# PCB-CMB-5-SHLD.net
KiCad netlist of a schematic drawn in EAGLE
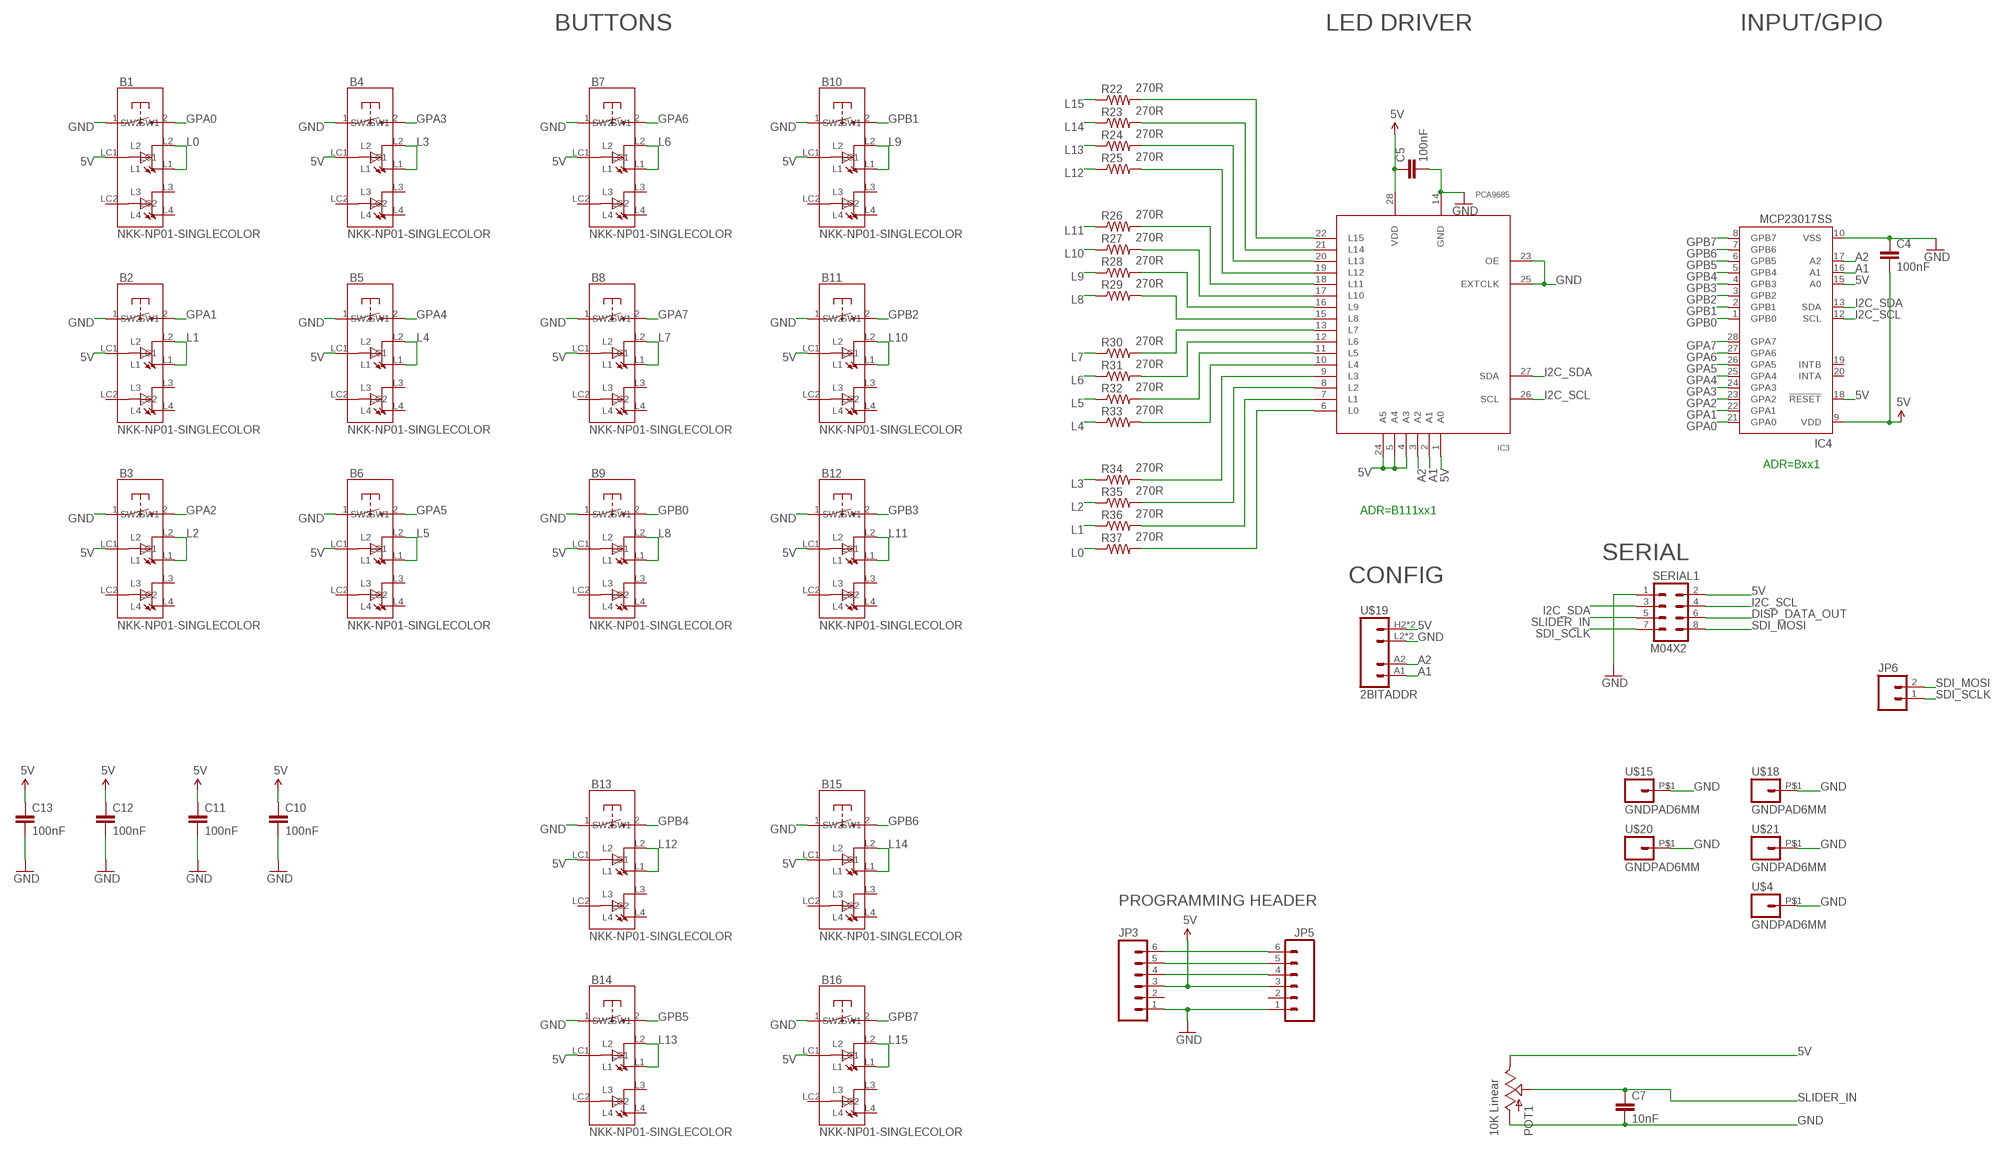
[diagram p0: schematic, sheet 1, part 1 of 3]
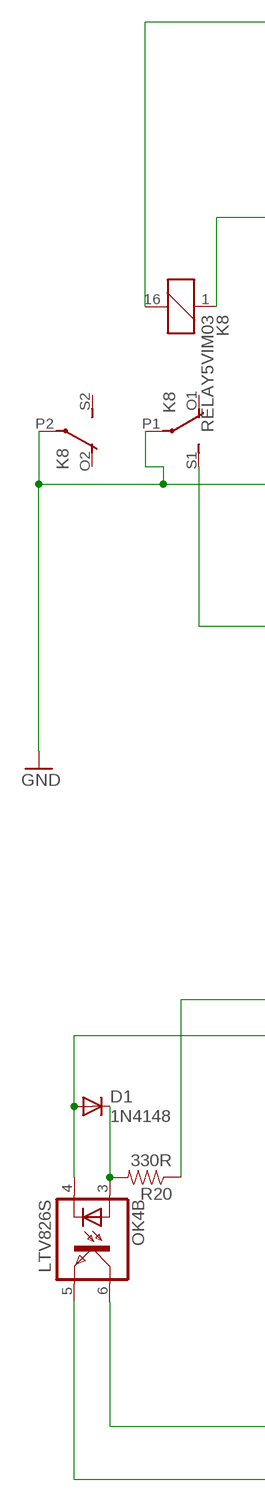
[diagram p1: schematic, sheet 1, part 2 of 3]
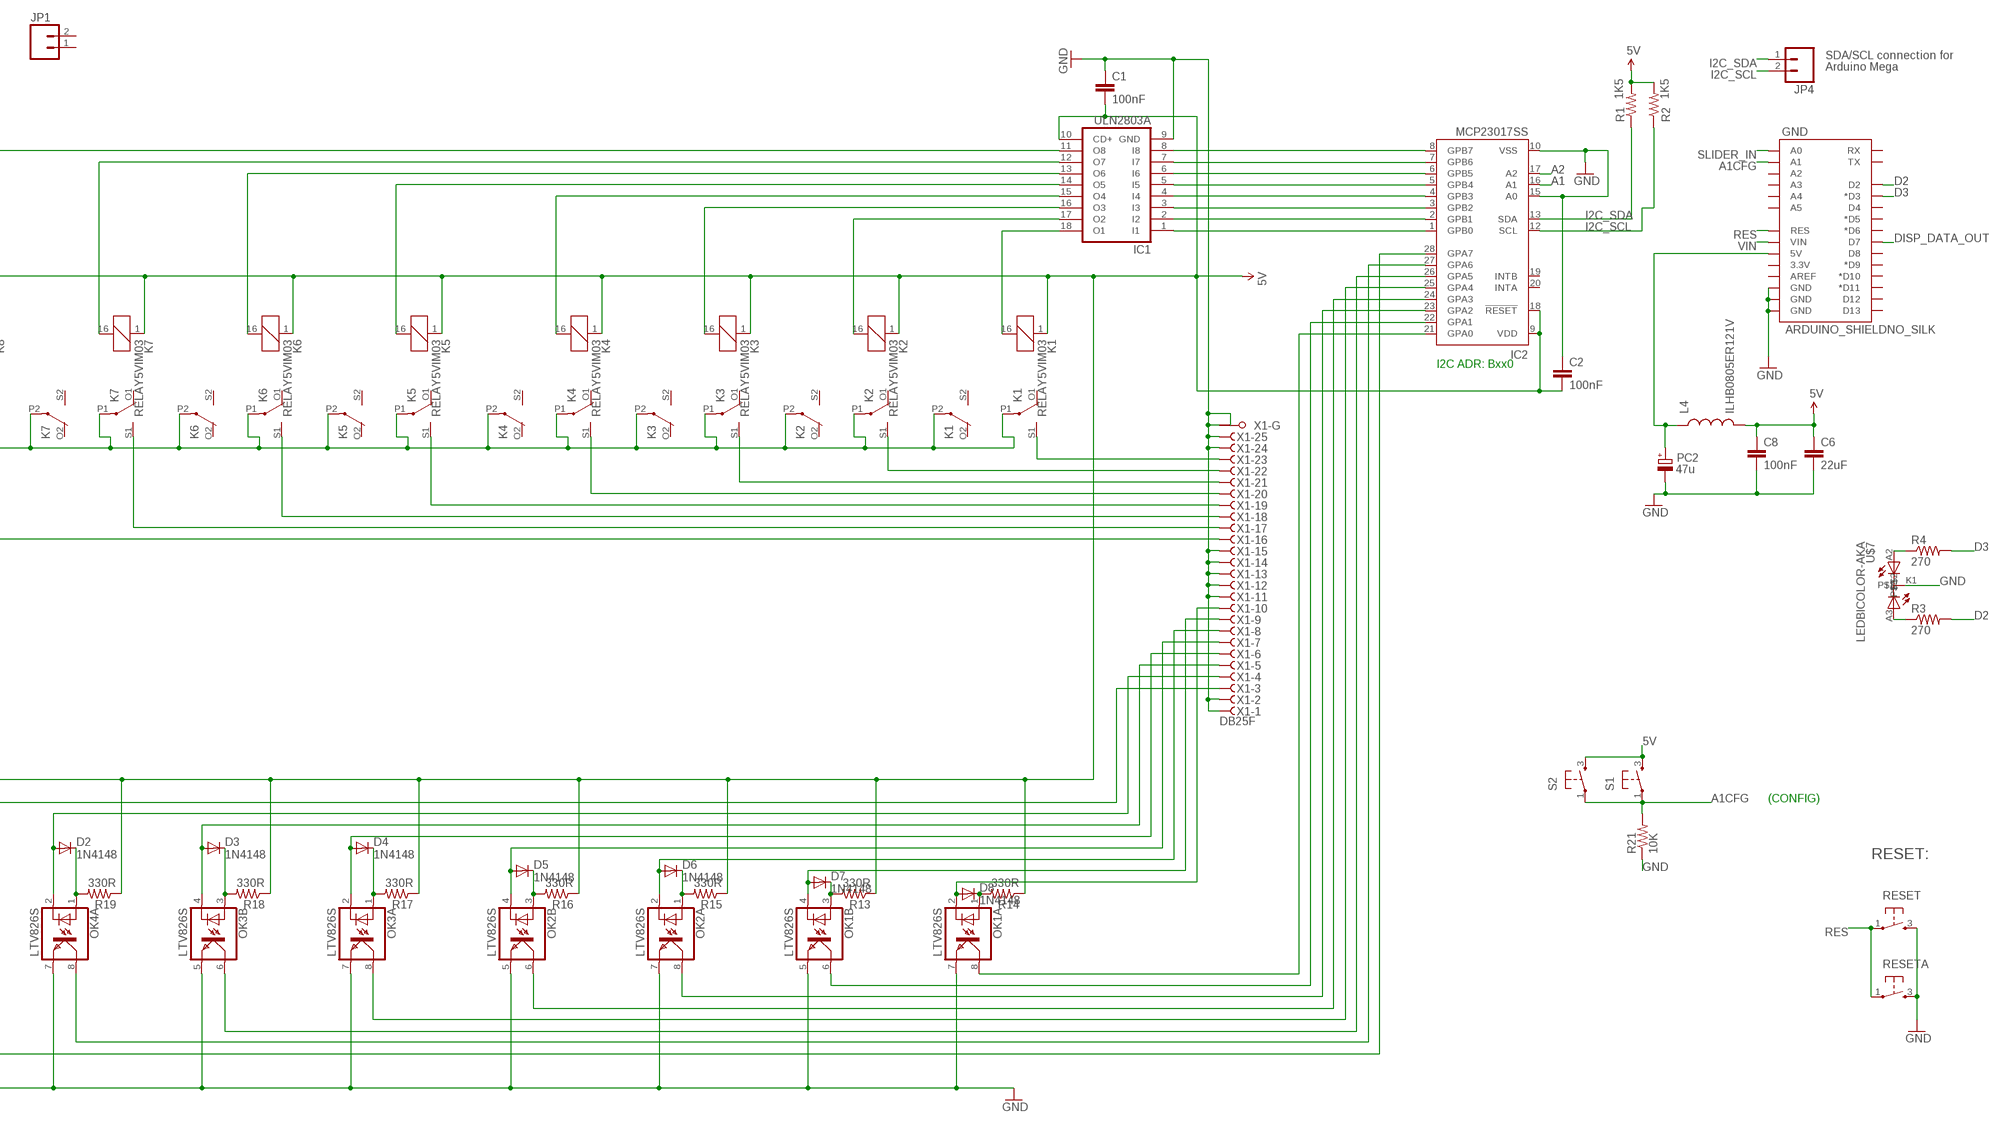
[diagram p2: schematic, sheet 1, part 3 of 3]

(export (version "E")
  (design (tool "Eeschema 10.0.6"))
  (components
    (comp (ref "B1")
      (value "NKK-NP01-SINGLECOLOR")
      (footprint "eagle-import:NKK-NP01")
      (libsource (lib "eagle-import") (part "NKK-NP01-SINGLECOLOR"))
    )
    (comp (ref "B2")
      (value "NKK-NP01-SINGLECOLOR")
      (footprint "eagle-import:NKK-NP01")
      (libsource (lib "eagle-import") (part "NKK-NP01-SINGLECOLOR"))
    )
    (comp (ref "B3")
      (value "NKK-NP01-SINGLECOLOR")
      (footprint "eagle-import:NKK-NP01")
      (libsource (lib "eagle-import") (part "NKK-NP01-SINGLECOLOR"))
    )
    (comp (ref "B4")
      (value "NKK-NP01-SINGLECOLOR")
      (footprint "eagle-import:NKK-NP01")
      (libsource (lib "eagle-import") (part "NKK-NP01-SINGLECOLOR"))
    )
    (comp (ref "B5")
      (value "NKK-NP01-SINGLECOLOR")
      (footprint "eagle-import:NKK-NP01")
      (libsource (lib "eagle-import") (part "NKK-NP01-SINGLECOLOR"))
    )
    (comp (ref "B6")
      (value "NKK-NP01-SINGLECOLOR")
      (footprint "eagle-import:NKK-NP01")
      (libsource (lib "eagle-import") (part "NKK-NP01-SINGLECOLOR"))
    )
    (comp (ref "B7")
      (value "NKK-NP01-SINGLECOLOR")
      (footprint "eagle-import:NKK-NP01")
      (libsource (lib "eagle-import") (part "NKK-NP01-SINGLECOLOR"))
    )
    (comp (ref "B8")
      (value "NKK-NP01-SINGLECOLOR")
      (footprint "eagle-import:NKK-NP01")
      (libsource (lib "eagle-import") (part "NKK-NP01-SINGLECOLOR"))
    )
    (comp (ref "B9")
      (value "NKK-NP01-SINGLECOLOR")
      (footprint "eagle-import:NKK-NP01")
      (libsource (lib "eagle-import") (part "NKK-NP01-SINGLECOLOR"))
    )
    (comp (ref "B10")
      (value "NKK-NP01-SINGLECOLOR")
      (footprint "eagle-import:NKK-NP01")
      (libsource (lib "eagle-import") (part "NKK-NP01-SINGLECOLOR"))
    )
    (comp (ref "B11")
      (value "NKK-NP01-SINGLECOLOR")
      (footprint "eagle-import:NKK-NP01")
      (libsource (lib "eagle-import") (part "NKK-NP01-SINGLECOLOR"))
    )
    (comp (ref "B12")
      (value "NKK-NP01-SINGLECOLOR")
      (footprint "eagle-import:NKK-NP01")
      (libsource (lib "eagle-import") (part "NKK-NP01-SINGLECOLOR"))
    )
    (comp (ref "B13")
      (value "NKK-NP01-SINGLECOLOR")
      (footprint "eagle-import:NKK-NP01")
      (libsource (lib "eagle-import") (part "NKK-NP01-SINGLECOLOR"))
    )
    (comp (ref "B14")
      (value "NKK-NP01-SINGLECOLOR")
      (footprint "eagle-import:NKK-NP01")
      (libsource (lib "eagle-import") (part "NKK-NP01-SINGLECOLOR"))
    )
    (comp (ref "B15")
      (value "NKK-NP01-SINGLECOLOR")
      (footprint "eagle-import:NKK-NP01")
      (libsource (lib "eagle-import") (part "NKK-NP01-SINGLECOLOR"))
    )
    (comp (ref "B16")
      (value "NKK-NP01-SINGLECOLOR")
      (footprint "eagle-import:NKK-NP01")
      (libsource (lib "eagle-import") (part "NKK-NP01-SINGLECOLOR"))
    )
    (comp (ref "C1")
      (value "100nF")
      (footprint "eagle-import:0805")
      (libsource (lib "eagle-import") (part "CAP0805"))
    )
    (comp (ref "C2")
      (value "100nF")
      (footprint "eagle-import:0603-CAP")
      (libsource (lib "eagle-import") (part "CAP0603-CAP"))
    )
    (comp (ref "C4")
      (value "100nF")
      (footprint "eagle-import:0603-CAP")
      (libsource (lib "eagle-import") (part "CAP0603-CAP"))
    )
    (comp (ref "C5")
      (value "100nF")
      (footprint "eagle-import:0603-CAP")
      (libsource (lib "eagle-import") (part "CAP0603-CAP"))
    )
    (comp (ref "C6")
      (value "22uF")
      (footprint "eagle-import:0805")
      (libsource (lib "eagle-import") (part "CAP0805"))
    )
    (comp (ref "C7")
      (value "10nF")
      (footprint "eagle-import:0603-CAP")
      (libsource (lib "eagle-import") (part "CAP0603-CAP"))
    )
    (comp (ref "C8")
      (value "100nF")
      (footprint "eagle-import:0603-CAP")
      (libsource (lib "eagle-import") (part "CAP0603-CAP"))
    )
    (comp (ref "C10")
      (value "100nF")
      (footprint "eagle-import:0603-CAP")
      (libsource (lib "eagle-import") (part "CAP0603-CAP"))
    )
    (comp (ref "C11")
      (value "100nF")
      (footprint "eagle-import:0603-CAP")
      (libsource (lib "eagle-import") (part "CAP0603-CAP"))
    )
    (comp (ref "C12")
      (value "100nF")
      (footprint "eagle-import:0603-CAP")
      (libsource (lib "eagle-import") (part "CAP0603-CAP"))
    )
    (comp (ref "C13")
      (value "100nF")
      (footprint "eagle-import:0603-CAP")
      (libsource (lib "eagle-import") (part "CAP0603-CAP"))
    )
    (comp (ref "D1")
      (value "1N4148")
      (footprint "eagle-import:SOD-323")
      (libsource (lib "eagle-import") (part "DIODESOD"))
    )
    (comp (ref "D2")
      (value "1N4148")
      (footprint "eagle-import:SOD-323")
      (libsource (lib "eagle-import") (part "DIODESOD"))
    )
    (comp (ref "D3")
      (value "1N4148")
      (footprint "eagle-import:SOD-323")
      (libsource (lib "eagle-import") (part "DIODESOD"))
    )
    (comp (ref "D4")
      (value "1N4148")
      (footprint "eagle-import:SOD-323")
      (libsource (lib "eagle-import") (part "DIODESOD"))
    )
    (comp (ref "D5")
      (value "1N4148")
      (footprint "eagle-import:SOD-323")
      (libsource (lib "eagle-import") (part "DIODESOD"))
    )
    (comp (ref "D6")
      (value "1N4148")
      (footprint "eagle-import:SOD-323")
      (libsource (lib "eagle-import") (part "DIODESOD"))
    )
    (comp (ref "D7")
      (value "1N4148")
      (footprint "eagle-import:SOD-323")
      (libsource (lib "eagle-import") (part "DIODESOD"))
    )
    (comp (ref "D8")
      (value "1N4148")
      (footprint "eagle-import:SOD-323")
      (libsource (lib "eagle-import") (part "DIODESOD"))
    )
    (comp (ref "GND")
      (value "ARDUINO_SHIELDNO_SILK")
      (footprint "eagle-import:DUEMILANOVE_VIAS")
      (libsource (lib "eagle-import") (part "ARDUINO_SHIELDNO_SILK"))
    )
    (comp (ref "IC1")
      (value "ULN2803A")
      (footprint "eagle-import:SO18W")
      (libsource (lib "eagle-import") (part "ULN2803ASO18W"))
    )
    (comp (ref "IC2")
      (value "MCP23017SS")
      (footprint "eagle-import:SSOP28")
      (fields (field (name "MF") "MICROCHIP") (field (name "MPN") "MCP23017-E/SS"))
      (libsource (lib "eagle-import") (part "MCP23017SS"))
    )
    (comp (ref "IC3")
      (value "PCA9685")
      (footprint "eagle-import:TSSOP28")
      (libsource (lib "eagle-import") (part "PCA9685"))
    )
    (comp (ref "IC4")
      (value "MCP23017SS")
      (footprint "eagle-import:SSOP28")
      (fields
        (field (name "MF") "MICROCHIP")
        (field (name "MPN") "MCP23017-E/SS")
        (field (name "MPN_1") "MCP23017-E/SS")
        (field (name "OC_FARNELL") "1467674")
        (field (name "OC_NEWARK") "31K2960")
      )
      (libsource (lib "eagle-import") (part "MCP23017SS"))
    )
    (comp (ref "JP1")
      (value "M02PTH")
      (footprint "eagle-import:1X02")
      (libsource (lib "eagle-import") (part "M02PTH"))
    )
    (comp (ref "JP3")
      (value "M06POLAR")
      (footprint "eagle-import:MOLEX-1X6")
      (libsource (lib "eagle-import") (part "M06POLAR"))
    )
    (comp (ref "JP4")
      (value "M02PTH")
      (footprint "eagle-import:1X02")
      (libsource (lib "eagle-import") (part "M02PTH"))
    )
    (comp (ref "JP5")
      (value "M06POLAR")
      (footprint "eagle-import:MOLEX-1X6")
      (libsource (lib "eagle-import") (part "M06POLAR"))
    )
    (comp (ref "JP6")
      (value "M02PTH")
      (footprint "eagle-import:1X02")
      (libsource (lib "eagle-import") (part "M02PTH"))
    )
    (comp (ref "K1")
      (value "RELAY5VIM03")
      (footprint "eagle-import:DS2Y")
      (libsource (lib "eagle-import") (part "RELAY5VIM03"))
    )
    (comp (ref "K2")
      (value "RELAY5VIM03")
      (footprint "eagle-import:DS2Y")
      (libsource (lib "eagle-import") (part "RELAY5VIM03"))
    )
    (comp (ref "K3")
      (value "RELAY5VIM03")
      (footprint "eagle-import:DS2Y")
      (libsource (lib "eagle-import") (part "RELAY5VIM03"))
    )
    (comp (ref "K4")
      (value "RELAY5VIM03")
      (footprint "eagle-import:DS2Y")
      (libsource (lib "eagle-import") (part "RELAY5VIM03"))
    )
    (comp (ref "K5")
      (value "RELAY5VIM03")
      (footprint "eagle-import:DS2Y")
      (libsource (lib "eagle-import") (part "RELAY5VIM03"))
    )
    (comp (ref "K6")
      (value "RELAY5VIM03")
      (footprint "eagle-import:DS2Y")
      (libsource (lib "eagle-import") (part "RELAY5VIM03"))
    )
    (comp (ref "K7")
      (value "RELAY5VIM03")
      (footprint "eagle-import:DS2Y")
      (libsource (lib "eagle-import") (part "RELAY5VIM03"))
    )
    (comp (ref "K8")
      (value "RELAY5VIM03")
      (footprint "eagle-import:DS2Y")
      (libsource (lib "eagle-import") (part "RELAY5VIM03"))
    )
    (comp (ref "L4")
      (value "ILHB0805ER121V")
      (footprint "eagle-import:0805")
      (libsource (lib "eagle-import") (part "INDUCTOR0805"))
    )
    (comp (ref "OK1")
      (value "LTV826S")
      (footprint "eagle-import:DIL8-SMD")
      (libsource (lib "eagle-import") (part "LTV826S"))
    )
    (comp (ref "OK2")
      (value "LTV826S")
      (footprint "eagle-import:DIL8-SMD")
      (libsource (lib "eagle-import") (part "LTV826S"))
    )
    (comp (ref "OK3")
      (value "LTV826S")
      (footprint "eagle-import:DIL8-SMD")
      (libsource (lib "eagle-import") (part "LTV826S"))
    )
    (comp (ref "OK4")
      (value "LTV826S")
      (footprint "eagle-import:DIL8-SMD")
      (libsource (lib "eagle-import") (part "LTV826S"))
    )
    (comp (ref "PC2")
      (value "47u")
      (footprint "eagle-import:PANASONIC_D")
      (libsource (lib "eagle-import") (part "CPOL-EUD"))
    )
    (comp (ref "POT1")
      (value "10K Linear")
      (footprint "eagle-import:SLIDER20")
      (libsource (lib "eagle-import") (part "SLIDER20"))
    )
    (comp (ref "R1")
      (value "1K5")
      (footprint "eagle-import:0603-RES")
      (libsource (lib "eagle-import") (part "RESISTOR0603-RES"))
    )
    (comp (ref "R2")
      (value "1K5")
      (footprint "eagle-import:0603-RES")
      (libsource (lib "eagle-import") (part "RESISTOR0603-RES"))
    )
    (comp (ref "R3")
      (value "270")
      (footprint "eagle-import:0603-RES")
      (libsource (lib "eagle-import") (part "RESISTOR0603-RES"))
    )
    (comp (ref "R4")
      (value "270")
      (footprint "eagle-import:0603-RES")
      (libsource (lib "eagle-import") (part "RESISTOR0603-RES"))
    )
    (comp (ref "R13")
      (value "330R")
      (footprint "eagle-import:0603-RES")
      (libsource (lib "eagle-import") (part "RESISTOR0603-RES"))
    )
    (comp (ref "R14")
      (value "330R")
      (footprint "eagle-import:0603-RES")
      (libsource (lib "eagle-import") (part "RESISTOR0603-RES"))
    )
    (comp (ref "R15")
      (value "330R")
      (footprint "eagle-import:0603-RES")
      (libsource (lib "eagle-import") (part "RESISTOR0603-RES"))
    )
    (comp (ref "R16")
      (value "330R")
      (footprint "eagle-import:0603-RES")
      (libsource (lib "eagle-import") (part "RESISTOR0603-RES"))
    )
    (comp (ref "R17")
      (value "330R")
      (footprint "eagle-import:0603-RES")
      (libsource (lib "eagle-import") (part "RESISTOR0603-RES"))
    )
    (comp (ref "R18")
      (value "330R")
      (footprint "eagle-import:0603-RES")
      (libsource (lib "eagle-import") (part "RESISTOR0603-RES"))
    )
    (comp (ref "R19")
      (value "330R")
      (footprint "eagle-import:0603-RES")
      (libsource (lib "eagle-import") (part "RESISTOR0603-RES"))
    )
    (comp (ref "R20")
      (value "330R")
      (footprint "eagle-import:0603-RES")
      (libsource (lib "eagle-import") (part "RESISTOR0603-RES"))
    )
    (comp (ref "R21")
      (value "10K")
      (footprint "eagle-import:0603-RES")
      (libsource (lib "eagle-import") (part "RESISTOR0603-RES"))
    )
    (comp (ref "R22")
      (value "270R")
      (footprint "eagle-import:0603-RES")
      (libsource (lib "eagle-import") (part "RESISTOR0603-RES"))
    )
    (comp (ref "R23")
      (value "270R")
      (footprint "eagle-import:0603-RES")
      (libsource (lib "eagle-import") (part "RESISTOR0603-RES"))
    )
    (comp (ref "R24")
      (value "270R")
      (footprint "eagle-import:0603-RES")
      (libsource (lib "eagle-import") (part "RESISTOR0603-RES"))
    )
    (comp (ref "R25")
      (value "270R")
      (footprint "eagle-import:0603-RES")
      (libsource (lib "eagle-import") (part "RESISTOR0603-RES"))
    )
    (comp (ref "R26")
      (value "270R")
      (footprint "eagle-import:0603-RES")
      (libsource (lib "eagle-import") (part "RESISTOR0603-RES"))
    )
    (comp (ref "R27")
      (value "270R")
      (footprint "eagle-import:0603-RES")
      (libsource (lib "eagle-import") (part "RESISTOR0603-RES"))
    )
    (comp (ref "R28")
      (value "270R")
      (footprint "eagle-import:0603-RES")
      (libsource (lib "eagle-import") (part "RESISTOR0603-RES"))
    )
    (comp (ref "R29")
      (value "270R")
      (footprint "eagle-import:0603-RES")
      (libsource (lib "eagle-import") (part "RESISTOR0603-RES"))
    )
    (comp (ref "R30")
      (value "270R")
      (footprint "eagle-import:0603-RES")
      (libsource (lib "eagle-import") (part "RESISTOR0603-RES"))
    )
    (comp (ref "R31")
      (value "270R")
      (footprint "eagle-import:0603-RES")
      (libsource (lib "eagle-import") (part "RESISTOR0603-RES"))
    )
    (comp (ref "R32")
      (value "270R")
      (footprint "eagle-import:0603-RES")
      (libsource (lib "eagle-import") (part "RESISTOR0603-RES"))
    )
    (comp (ref "R33")
      (value "270R")
      (footprint "eagle-import:0603-RES")
      (libsource (lib "eagle-import") (part "RESISTOR0603-RES"))
    )
    (comp (ref "R34")
      (value "270R")
      (footprint "eagle-import:0603-RES")
      (libsource (lib "eagle-import") (part "RESISTOR0603-RES"))
    )
    (comp (ref "R35")
      (value "270R")
      (footprint "eagle-import:0603-RES")
      (libsource (lib "eagle-import") (part "RESISTOR0603-RES"))
    )
    (comp (ref "R36")
      (value "270R")
      (footprint "eagle-import:0603-RES")
      (libsource (lib "eagle-import") (part "RESISTOR0603-RES"))
    )
    (comp (ref "R37")
      (value "270R")
      (footprint "eagle-import:0603-RES")
      (libsource (lib "eagle-import") (part "RESISTOR0603-RES"))
    )
    (comp (ref "RESET")
      (value "TAC_SWITCH")
      (footprint "eagle-import:PUSHBUTTON")
      (libsource (lib "eagle-import") (part "TAC_SWITCH"))
    )
    (comp (ref "RESETA")
      (value "TAC_SWITCH")
      (footprint "eagle-import:PUSHBUTTON")
      (libsource (lib "eagle-import") (part "TAC_SWITCH"))
    )
    (comp (ref "S1")
      (value "TAC_SWITCH")
      (footprint "eagle-import:PUSHBUTTON")
      (libsource (lib "eagle-import") (part "TAC_SWITCH"))
    )
    (comp (ref "S2")
      (value "TAC_SWITCH")
      (footprint "eagle-import:PUSHBUTTON")
      (libsource (lib "eagle-import") (part "TAC_SWITCH"))
    )
    (comp (ref "SERIAL1")
      (value "M04X2")
      (footprint "eagle-import:2X4")
      (libsource (lib "eagle-import") (part "M04X2"))
    )
    (comp (ref "U$4")
      (value "GNDPAD6MM")
      (footprint "eagle-import:3.2MMPAD6MM")
      (libsource (lib "eagle-import") (part "GNDPAD6MM"))
    )
    (comp (ref "U$7")
      (value "LEDBICOLOR-AKA")
      (footprint "eagle-import:LED5MM-BICOLOR")
      (libsource (lib "eagle-import") (part "LEDBICOLOR-AKA"))
    )
    (comp (ref "U$15")
      (value "GNDPAD6MM")
      (footprint "eagle-import:3.2MMPAD6MM")
      (libsource (lib "eagle-import") (part "GNDPAD6MM"))
    )
    (comp (ref "U$18")
      (value "GNDPAD6MM")
      (footprint "eagle-import:3.2MMPAD6MM")
      (libsource (lib "eagle-import") (part "GNDPAD6MM"))
    )
    (comp (ref "U$19")
      (value "2BITADDR")
      (footprint "eagle-import:2BITADDR")
      (libsource (lib "eagle-import") (part "2BITADDR"))
    )
    (comp (ref "U$20")
      (value "GNDPAD6MM")
      (footprint "eagle-import:3.2MMPAD6MM")
      (libsource (lib "eagle-import") (part "GNDPAD6MM"))
    )
    (comp (ref "U$21")
      (value "GNDPAD6MM")
      (footprint "eagle-import:3.2MMPAD6MM")
      (libsource (lib "eagle-import") (part "GNDPAD6MM"))
    )
    (comp (ref "X1")
      (value "DB25F")
      (footprint "eagle-import:F25HP")
      (libsource (lib "eagle-import") (part "F25HPS"))
    )
  )
  (nets
    (net (code "1") (name "5V") (class "Default")
      (node (ref "B1") (pin "LC1") (pinfunction "LC1_LC1") (pintype "bidirectional"))
      (node (ref "B10") (pin "LC1") (pinfunction "LC1_LC1") (pintype "bidirectional"))
      (node (ref "B11") (pin "LC1") (pinfunction "LC1_LC1") (pintype "bidirectional"))
      (node (ref "B12") (pin "LC1") (pinfunction "LC1_LC1") (pintype "bidirectional"))
      (node (ref "B13") (pin "LC1") (pinfunction "LC1_LC1") (pintype "bidirectional"))
      (node (ref "B14") (pin "LC1") (pinfunction "LC1_LC1") (pintype "bidirectional"))
      (node (ref "B15") (pin "LC1") (pinfunction "LC1_LC1") (pintype "bidirectional"))
      (node (ref "B16") (pin "LC1") (pinfunction "LC1_LC1") (pintype "bidirectional"))
      (node (ref "B2") (pin "LC1") (pinfunction "LC1_LC1") (pintype "bidirectional"))
      (node (ref "B3") (pin "LC1") (pinfunction "LC1_LC1") (pintype "bidirectional"))
      (node (ref "B4") (pin "LC1") (pinfunction "LC1_LC1") (pintype "bidirectional"))
      (node (ref "B5") (pin "LC1") (pinfunction "LC1_LC1") (pintype "bidirectional"))
      (node (ref "B6") (pin "LC1") (pinfunction "LC1_LC1") (pintype "bidirectional"))
      (node (ref "B7") (pin "LC1") (pinfunction "LC1_LC1") (pintype "bidirectional"))
      (node (ref "B8") (pin "LC1") (pinfunction "LC1_LC1") (pintype "bidirectional"))
      (node (ref "B9") (pin "LC1") (pinfunction "LC1_LC1") (pintype "bidirectional"))
      (node (ref "C1") (pin "2") (pinfunction "2_2") (pintype "passive"))
      (node (ref "C10") (pin "1") (pinfunction "1_1") (pintype "passive"))
      (node (ref "C11") (pin "1") (pinfunction "1_1") (pintype "passive"))
      (node (ref "C12") (pin "1") (pinfunction "1_1") (pintype "passive"))
      (node (ref "C13") (pin "1") (pinfunction "1_1") (pintype "passive"))
      (node (ref "C2") (pin "2") (pinfunction "2_2") (pintype "passive"))
      (node (ref "C4") (pin "2") (pinfunction "2_2") (pintype "passive"))
      (node (ref "C5") (pin "1") (pinfunction "1_1") (pintype "passive"))
      (node (ref "C6") (pin "1") (pinfunction "1_1") (pintype "passive"))
      (node (ref "C8") (pin "1") (pinfunction "1_1") (pintype "passive"))
      (node (ref "IC1") (pin "10") (pinfunction "CD+_10") (pintype "passive"))
      (node (ref "IC2") (pin "18") (pinfunction "~{RESET}_18") (pintype "input"))
      (node (ref "IC2") (pin "9") (pinfunction "VDD_9") (pintype "power_in"))
      (node (ref "IC3") (pin "1") (pinfunction "A0_1") (pintype "input"))
      (node (ref "IC3") (pin "24") (pinfunction "A5_24") (pintype "input"))
      (node (ref "IC3") (pin "28") (pinfunction "VDD_28") (pintype "power_in"))
      (node (ref "IC3") (pin "4") (pinfunction "A3_4") (pintype "input"))
      (node (ref "IC3") (pin "5") (pinfunction "A4_5") (pintype "input"))
      (node (ref "IC4") (pin "15") (pinfunction "A0_15") (pintype "input"))
      (node (ref "IC4") (pin "18") (pinfunction "~{RESET}_18") (pintype "input"))
      (node (ref "IC4") (pin "9") (pinfunction "VDD_9") (pintype "power_in"))
      (node (ref "JP3") (pin "3") (pinfunction "3_3") (pintype "passive"))
      (node (ref "JP5") (pin "3") (pinfunction "3_3") (pintype "passive"))
      (node (ref "K1") (pin "1") (pinfunction "1_1") (pintype "passive"))
      (node (ref "K2") (pin "1") (pinfunction "1_1") (pintype "passive"))
      (node (ref "K3") (pin "1") (pinfunction "1_1") (pintype "passive"))
      (node (ref "K4") (pin "1") (pinfunction "1_1") (pintype "passive"))
      (node (ref "K5") (pin "1") (pinfunction "1_1") (pintype "passive"))
      (node (ref "K6") (pin "1") (pinfunction "1_1") (pintype "passive"))
      (node (ref "K7") (pin "1") (pinfunction "1_1") (pintype "passive"))
      (node (ref "K8") (pin "1") (pinfunction "1_1") (pintype "passive"))
      (node (ref "L4") (pin "2") (pinfunction "2_2") (pintype "passive"))
      (node (ref "POT1") (pin "1") (pinfunction "E_1") (pintype "passive"))
      (node (ref "R1") (pin "2") (pinfunction "2_2") (pintype "passive"))
      (node (ref "R13") (pin "1") (pinfunction "1_1") (pintype "passive"))
      (node (ref "R14") (pin "1") (pinfunction "1_1") (pintype "passive"))
      (node (ref "R15") (pin "1") (pinfunction "1_1") (pintype "passive"))
      (node (ref "R16") (pin "1") (pinfunction "1_1") (pintype "passive"))
      (node (ref "R17") (pin "1") (pinfunction "1_1") (pintype "passive"))
      (node (ref "R18") (pin "1") (pinfunction "1_1") (pintype "passive"))
      (node (ref "R19") (pin "1") (pinfunction "1_1") (pintype "passive"))
      (node (ref "R2") (pin "2") (pinfunction "2_2") (pintype "passive"))
      (node (ref "R20") (pin "1") (pinfunction "1_1") (pintype "passive"))
      (node (ref "S1") (pin "3") (pinfunction "3_3") (pintype "passive"))
      (node (ref "S2") (pin "3") (pinfunction "3_3") (pintype "passive"))
      (node (ref "SERIAL1") (pin "2") (pinfunction "2_2") (pintype "passive"))
      (node (ref "U$19") (pin "H2") (pinfunction "VCC_H2") (pintype "passive"))
      (node (ref "U$19") (pin "H3") (pinfunction "VCC_H3") (pintype "passive"))
    )
    (net (code "2") (name "A1") (class "Default")
      (node (ref "IC2") (pin "16") (pinfunction "A1_16") (pintype "input"))
      (node (ref "IC3") (pin "2") (pinfunction "A1_2") (pintype "input"))
      (node (ref "IC4") (pin "16") (pinfunction "A1_16") (pintype "input"))
      (node (ref "U$19") (pin "A1") (pinfunction "A1_A1") (pintype "passive"))
    )
    (net (code "3") (name "A1CFG") (class "Default")
      (node (ref "GND") (pin "A1") (pinfunction "A1_A1") (pintype "bidirectional"))
      (node (ref "R21") (pin "2") (pinfunction "2_2") (pintype "passive"))
      (node (ref "S1") (pin "1") (pinfunction "1_1") (pintype "passive"))
      (node (ref "S2") (pin "1") (pinfunction "1_1") (pintype "passive"))
    )
    (net (code "4") (name "A2") (class "Default")
      (node (ref "IC2") (pin "17") (pinfunction "A2_17") (pintype "input"))
      (node (ref "IC3") (pin "3") (pinfunction "A2_3") (pintype "input"))
      (node (ref "IC4") (pin "17") (pinfunction "A2_17") (pintype "input"))
      (node (ref "U$19") (pin "A2") (pinfunction "A2_A2") (pintype "passive"))
    )
    (net (code "5") (name "D2") (class "Default")
      (node (ref "GND") (pin "D2") (pinfunction "D2_D2") (pintype "bidirectional"))
      (node (ref "R3") (pin "2") (pinfunction "2_2") (pintype "passive"))
    )
    (net (code "6") (name "D3") (class "Default")
      (node (ref "GND") (pin "D3") (pinfunction "*D3_D3") (pintype "bidirectional"))
      (node (ref "R4") (pin "2") (pinfunction "2_2") (pintype "passive"))
    )
    (net (code "7") (name "DISP_DATA_OUT") (class "Default")
      (node (ref "GND") (pin "D7") (pinfunction "D7_D7") (pintype "bidirectional"))
      (node (ref "SERIAL1") (pin "6") (pinfunction "6_6") (pintype "passive"))
    )
    (net (code "8") (name "GND") (class "Default")
      (node (ref "B1") (pin "1") (pinfunction "SW1_1") (pintype "bidirectional"))
      (node (ref "B10") (pin "1") (pinfunction "SW1_1") (pintype "bidirectional"))
      (node (ref "B11") (pin "1") (pinfunction "SW1_1") (pintype "bidirectional"))
      (node (ref "B12") (pin "1") (pinfunction "SW1_1") (pintype "bidirectional"))
      (node (ref "B13") (pin "1") (pinfunction "SW1_1") (pintype "bidirectional"))
      (node (ref "B14") (pin "1") (pinfunction "SW1_1") (pintype "bidirectional"))
      (node (ref "B15") (pin "1") (pinfunction "SW1_1") (pintype "bidirectional"))
      (node (ref "B16") (pin "1") (pinfunction "SW1_1") (pintype "bidirectional"))
      (node (ref "B2") (pin "1") (pinfunction "SW1_1") (pintype "bidirectional"))
      (node (ref "B3") (pin "1") (pinfunction "SW1_1") (pintype "bidirectional"))
      (node (ref "B4") (pin "1") (pinfunction "SW1_1") (pintype "bidirectional"))
      (node (ref "B5") (pin "1") (pinfunction "SW1_1") (pintype "bidirectional"))
      (node (ref "B6") (pin "1") (pinfunction "SW1_1") (pintype "bidirectional"))
      (node (ref "B7") (pin "1") (pinfunction "SW1_1") (pintype "bidirectional"))
      (node (ref "B8") (pin "1") (pinfunction "SW1_1") (pintype "bidirectional"))
      (node (ref "B9") (pin "1") (pinfunction "SW1_1") (pintype "bidirectional"))
      (node (ref "C1") (pin "1") (pinfunction "1_1") (pintype "passive"))
      (node (ref "C10") (pin "2") (pinfunction "2_2") (pintype "passive"))
      (node (ref "C11") (pin "2") (pinfunction "2_2") (pintype "passive"))
      (node (ref "C12") (pin "2") (pinfunction "2_2") (pintype "passive"))
      (node (ref "C13") (pin "2") (pinfunction "2_2") (pintype "passive"))
      (node (ref "C2") (pin "1") (pinfunction "1_1") (pintype "passive"))
      (node (ref "C4") (pin "1") (pinfunction "1_1") (pintype "passive"))
      (node (ref "C5") (pin "2") (pinfunction "2_2") (pintype "passive"))
      (node (ref "C6") (pin "2") (pinfunction "2_2") (pintype "passive"))
      (node (ref "C7") (pin "2") (pinfunction "2_2") (pintype "passive"))
      (node (ref "C8") (pin "2") (pinfunction "2_2") (pintype "passive"))
      (node (ref "GND") (pin "GND@0") (pinfunction "GND_GND@0") (pintype "bidirectional"))
      (node (ref "GND") (pin "GND@1") (pinfunction "GND_GND@1") (pintype "bidirectional"))
      (node (ref "GND") (pin "GND@2") (pinfunction "GND_GND@2") (pintype "bidirectional"))
      (node (ref "IC1") (pin "9") (pinfunction "GND_9") (pintype "power_in"))
      (node (ref "IC2") (pin "10") (pinfunction "VSS_10") (pintype "power_in"))
      (node (ref "IC2") (pin "15") (pinfunction "A0_15") (pintype "input"))
      (node (ref "IC3") (pin "14") (pinfunction "GND_14") (pintype "power_in"))
      (node (ref "IC3") (pin "23") (pinfunction "OE_23") (pintype "input"))
      (node (ref "IC3") (pin "25") (pinfunction "EXTCLK_25") (pintype "input"))
      (node (ref "IC4") (pin "10") (pinfunction "VSS_10") (pintype "power_in"))
      (node (ref "JP3") (pin "1") (pinfunction "1_1") (pintype "passive"))
      (node (ref "JP5") (pin "1") (pinfunction "1_1") (pintype "passive"))
      (node (ref "K1") (pin "P1") (pinfunction "P_P1") (pintype "passive"))
      (node (ref "K1") (pin "P2") (pinfunction "P_P2") (pintype "passive"))
      (node (ref "K2") (pin "P1") (pinfunction "P_P1") (pintype "passive"))
      (node (ref "K2") (pin "P2") (pinfunction "P_P2") (pintype "passive"))
      (node (ref "K3") (pin "P1") (pinfunction "P_P1") (pintype "passive"))
      (node (ref "K3") (pin "P2") (pinfunction "P_P2") (pintype "passive"))
      (node (ref "K4") (pin "P1") (pinfunction "P_P1") (pintype "passive"))
      (node (ref "K4") (pin "P2") (pinfunction "P_P2") (pintype "passive"))
      (node (ref "K5") (pin "P1") (pinfunction "P_P1") (pintype "passive"))
      (node (ref "K5") (pin "P2") (pinfunction "P_P2") (pintype "passive"))
      (node (ref "K6") (pin "P1") (pinfunction "P_P1") (pintype "passive"))
      (node (ref "K6") (pin "P2") (pinfunction "P_P2") (pintype "passive"))
      (node (ref "K7") (pin "P1") (pinfunction "P_P1") (pintype "passive"))
      (node (ref "K7") (pin "P2") (pinfunction "P_P2") (pintype "passive"))
      (node (ref "K8") (pin "P1") (pinfunction "P_P1") (pintype "passive"))
      (node (ref "K8") (pin "P2") (pinfunction "P_P2") (pintype "passive"))
      (node (ref "OK1") (pin "5") (pinfunction "EMIT_5") (pintype "passive"))
      (node (ref "OK1") (pin "7") (pinfunction "EMIT_7") (pintype "passive"))
      (node (ref "OK2") (pin "5") (pinfunction "EMIT_5") (pintype "passive"))
      (node (ref "OK2") (pin "7") (pinfunction "EMIT_7") (pintype "passive"))
      (node (ref "OK3") (pin "5") (pinfunction "EMIT_5") (pintype "passive"))
      (node (ref "OK3") (pin "7") (pinfunction "EMIT_7") (pintype "passive"))
      (node (ref "OK4") (pin "5") (pinfunction "EMIT_5") (pintype "passive"))
      (node (ref "OK4") (pin "7") (pinfunction "EMIT_7") (pintype "passive"))
      (node (ref "PC2") (pin "-") (pinfunction "-_-") (pintype "passive"))
      (node (ref "POT1") (pin "3") (pinfunction "A_3") (pintype "passive"))
      (node (ref "R21") (pin "1") (pinfunction "1_1") (pintype "passive"))
      (node (ref "RESET") (pin "3") (pinfunction "3_3") (pintype "passive"))
      (node (ref "RESETA") (pin "3") (pinfunction "3_3") (pintype "passive"))
      (node (ref "SERIAL1") (pin "1") (pinfunction "1_1") (pintype "passive"))
      (node (ref "U$15") (pin "P$1") (pinfunction "1_P$1") (pintype "passive"))
      (node (ref "U$18") (pin "P$1") (pinfunction "1_P$1") (pintype "passive"))
      (node (ref "U$19") (pin "L2") (pinfunction "GND_L2") (pintype "passive"))
      (node (ref "U$19") (pin "L3") (pinfunction "GND_L3") (pintype "passive"))
      (node (ref "U$20") (pin "P$1") (pinfunction "1_P$1") (pintype "passive"))
      (node (ref "U$21") (pin "P$1") (pinfunction "1_P$1") (pintype "passive"))
      (node (ref "U$4") (pin "P$1") (pinfunction "1_P$1") (pintype "passive"))
      (node (ref "U$7") (pin "K1") (pinfunction "P$1_K1") (pintype "bidirectional"))
      (node (ref "X1") (pin "1") (pinfunction "F_1") (pintype "passive"))
      (node (ref "X1") (pin "11") (pinfunction "F_11") (pintype "passive"))
      (node (ref "X1") (pin "12") (pinfunction "F_12") (pintype "passive"))
      (node (ref "X1") (pin "13") (pinfunction "F_13") (pintype "passive"))
      (node (ref "X1") (pin "14") (pinfunction "F_14") (pintype "passive"))
      (node (ref "X1") (pin "15") (pinfunction "F_15") (pintype "passive"))
      (node (ref "X1") (pin "2") (pinfunction "F_2") (pintype "passive"))
      (node (ref "X1") (pin "24") (pinfunction "F_24") (pintype "passive"))
      (node (ref "X1") (pin "25") (pinfunction "F_25") (pintype "passive"))
      (node (ref "X1") (pin "G1") (pinfunction "G1_G1") (pintype "passive"))
      (node (ref "X1") (pin "G2") (pinfunction "G2_G2") (pintype "passive"))
    )
    (net (code "9") (name "GPA0") (class "Default")
      (node (ref "B1") (pin "2") (pinfunction "SW2_2") (pintype "bidirectional"))
      (node (ref "IC4") (pin "21") (pinfunction "GPA0_21") (pintype "bidirectional"))
    )
    (net (code "10") (name "GPA1") (class "Default")
      (node (ref "B2") (pin "2") (pinfunction "SW2_2") (pintype "bidirectional"))
      (node (ref "IC4") (pin "22") (pinfunction "GPA1_22") (pintype "bidirectional"))
    )
    (net (code "11") (name "GPA2") (class "Default")
      (node (ref "B3") (pin "2") (pinfunction "SW2_2") (pintype "bidirectional"))
      (node (ref "IC4") (pin "23") (pinfunction "GPA2_23") (pintype "bidirectional"))
    )
    (net (code "12") (name "GPA3") (class "Default")
      (node (ref "B4") (pin "2") (pinfunction "SW2_2") (pintype "bidirectional"))
      (node (ref "IC4") (pin "24") (pinfunction "GPA3_24") (pintype "bidirectional"))
    )
    (net (code "13") (name "GPA4") (class "Default")
      (node (ref "B5") (pin "2") (pinfunction "SW2_2") (pintype "bidirectional"))
      (node (ref "IC4") (pin "25") (pinfunction "GPA4_25") (pintype "bidirectional"))
    )
    (net (code "14") (name "GPA5") (class "Default")
      (node (ref "B6") (pin "2") (pinfunction "SW2_2") (pintype "bidirectional"))
      (node (ref "IC4") (pin "26") (pinfunction "GPA5_26") (pintype "bidirectional"))
    )
    (net (code "15") (name "GPA6") (class "Default")
      (node (ref "B7") (pin "2") (pinfunction "SW2_2") (pintype "bidirectional"))
      (node (ref "IC4") (pin "27") (pinfunction "GPA6_27") (pintype "bidirectional"))
    )
    (net (code "16") (name "GPA7") (class "Default")
      (node (ref "B8") (pin "2") (pinfunction "SW2_2") (pintype "bidirectional"))
      (node (ref "IC4") (pin "28") (pinfunction "GPA7_28") (pintype "bidirectional"))
    )
    (net (code "17") (name "GPB0") (class "Default")
      (node (ref "B9") (pin "2") (pinfunction "SW2_2") (pintype "bidirectional"))
      (node (ref "IC4") (pin "1") (pinfunction "GPB0_1") (pintype "bidirectional"))
    )
    (net (code "18") (name "GPB1") (class "Default")
      (node (ref "B10") (pin "2") (pinfunction "SW2_2") (pintype "bidirectional"))
      (node (ref "IC4") (pin "2") (pinfunction "GPB1_2") (pintype "bidirectional"))
    )
    (net (code "19") (name "GPB2") (class "Default")
      (node (ref "B11") (pin "2") (pinfunction "SW2_2") (pintype "bidirectional"))
      (node (ref "IC4") (pin "3") (pinfunction "GPB2_3") (pintype "bidirectional"))
    )
    (net (code "20") (name "GPB3") (class "Default")
      (node (ref "B12") (pin "2") (pinfunction "SW2_2") (pintype "bidirectional"))
      (node (ref "IC4") (pin "4") (pinfunction "GPB3_4") (pintype "bidirectional"))
    )
    (net (code "21") (name "GPB4") (class "Default")
      (node (ref "B13") (pin "2") (pinfunction "SW2_2") (pintype "bidirectional"))
      (node (ref "IC4") (pin "5") (pinfunction "GPB4_5") (pintype "bidirectional"))
    )
    (net (code "22") (name "GPB5") (class "Default")
      (node (ref "B14") (pin "2") (pinfunction "SW2_2") (pintype "bidirectional"))
      (node (ref "IC4") (pin "6") (pinfunction "GPB5_6") (pintype "bidirectional"))
    )
    (net (code "23") (name "GPB6") (class "Default")
      (node (ref "B15") (pin "2") (pinfunction "SW2_2") (pintype "bidirectional"))
      (node (ref "IC4") (pin "7") (pinfunction "GPB6_7") (pintype "bidirectional"))
    )
    (net (code "24") (name "GPB7") (class "Default")
      (node (ref "B16") (pin "2") (pinfunction "SW2_2") (pintype "bidirectional"))
      (node (ref "IC4") (pin "8") (pinfunction "GPB7_8") (pintype "bidirectional"))
    )
    (net (code "25") (name "I2C_SCL") (class "Default")
      (node (ref "IC2") (pin "12") (pinfunction "SCL_12") (pintype "input"))
      (node (ref "IC3") (pin "26") (pinfunction "SCL_26") (pintype "input"))
      (node (ref "IC4") (pin "12") (pinfunction "SCL_12") (pintype "input"))
      (node (ref "JP4") (pin "2") (pinfunction "2_2") (pintype "passive"))
      (node (ref "R2") (pin "1") (pinfunction "1_1") (pintype "passive"))
      (node (ref "SERIAL1") (pin "4") (pinfunction "4_4") (pintype "passive"))
    )
    (net (code "26") (name "I2C_SDA") (class "Default")
      (node (ref "IC2") (pin "13") (pinfunction "SDA_13") (pintype "bidirectional"))
      (node (ref "IC3") (pin "27") (pinfunction "SDA_27") (pintype "input"))
      (node (ref "IC4") (pin "13") (pinfunction "SDA_13") (pintype "bidirectional"))
      (node (ref "JP4") (pin "1") (pinfunction "1_1") (pintype "passive"))
      (node (ref "R1") (pin "1") (pinfunction "1_1") (pintype "passive"))
      (node (ref "SERIAL1") (pin "3") (pinfunction "3_3") (pintype "passive"))
    )
    (net (code "27") (name "L0") (class "Default")
      (node (ref "B1") (pin "L1") (pinfunction "L1_L1") (pintype "bidirectional"))
      (node (ref "B1") (pin "L2") (pinfunction "L2_L2") (pintype "bidirectional"))
      (node (ref "R37") (pin "1") (pinfunction "1_1") (pintype "passive"))
    )
    (net (code "28") (name "L1") (class "Default")
      (node (ref "B2") (pin "L1") (pinfunction "L1_L1") (pintype "bidirectional"))
      (node (ref "B2") (pin "L2") (pinfunction "L2_L2") (pintype "bidirectional"))
      (node (ref "R36") (pin "1") (pinfunction "1_1") (pintype "passive"))
    )
    (net (code "29") (name "L2") (class "Default")
      (node (ref "B3") (pin "L1") (pinfunction "L1_L1") (pintype "bidirectional"))
      (node (ref "B3") (pin "L2") (pinfunction "L2_L2") (pintype "bidirectional"))
      (node (ref "R35") (pin "1") (pinfunction "1_1") (pintype "passive"))
    )
    (net (code "30") (name "L3") (class "Default")
      (node (ref "B4") (pin "L1") (pinfunction "L1_L1") (pintype "bidirectional"))
      (node (ref "B4") (pin "L2") (pinfunction "L2_L2") (pintype "bidirectional"))
      (node (ref "R34") (pin "1") (pinfunction "1_1") (pintype "passive"))
    )
    (net (code "31") (name "L4") (class "Default")
      (node (ref "B5") (pin "L1") (pinfunction "L1_L1") (pintype "bidirectional"))
      (node (ref "B5") (pin "L2") (pinfunction "L2_L2") (pintype "bidirectional"))
      (node (ref "R33") (pin "1") (pinfunction "1_1") (pintype "passive"))
    )
    (net (code "32") (name "L5") (class "Default")
      (node (ref "B6") (pin "L1") (pinfunction "L1_L1") (pintype "bidirectional"))
      (node (ref "B6") (pin "L2") (pinfunction "L2_L2") (pintype "bidirectional"))
      (node (ref "R32") (pin "1") (pinfunction "1_1") (pintype "passive"))
    )
    (net (code "33") (name "L6") (class "Default")
      (node (ref "B7") (pin "L1") (pinfunction "L1_L1") (pintype "bidirectional"))
      (node (ref "B7") (pin "L2") (pinfunction "L2_L2") (pintype "bidirectional"))
      (node (ref "R31") (pin "1") (pinfunction "1_1") (pintype "passive"))
    )
    (net (code "34") (name "L7") (class "Default")
      (node (ref "B8") (pin "L1") (pinfunction "L1_L1") (pintype "bidirectional"))
      (node (ref "B8") (pin "L2") (pinfunction "L2_L2") (pintype "bidirectional"))
      (node (ref "R30") (pin "1") (pinfunction "1_1") (pintype "passive"))
    )
    (net (code "35") (name "L8") (class "Default")
      (node (ref "B9") (pin "L1") (pinfunction "L1_L1") (pintype "bidirectional"))
      (node (ref "B9") (pin "L2") (pinfunction "L2_L2") (pintype "bidirectional"))
      (node (ref "R29") (pin "1") (pinfunction "1_1") (pintype "passive"))
    )
    (net (code "36") (name "L9") (class "Default")
      (node (ref "B10") (pin "L1") (pinfunction "L1_L1") (pintype "bidirectional"))
      (node (ref "B10") (pin "L2") (pinfunction "L2_L2") (pintype "bidirectional"))
      (node (ref "R28") (pin "1") (pinfunction "1_1") (pintype "passive"))
    )
    (net (code "37") (name "L10") (class "Default")
      (node (ref "B11") (pin "L1") (pinfunction "L1_L1") (pintype "bidirectional"))
      (node (ref "B11") (pin "L2") (pinfunction "L2_L2") (pintype "bidirectional"))
      (node (ref "R27") (pin "1") (pinfunction "1_1") (pintype "passive"))
    )
    (net (code "38") (name "L11") (class "Default")
      (node (ref "B12") (pin "L1") (pinfunction "L1_L1") (pintype "bidirectional"))
      (node (ref "B12") (pin "L2") (pinfunction "L2_L2") (pintype "bidirectional"))
      (node (ref "R26") (pin "1") (pinfunction "1_1") (pintype "passive"))
    )
    (net (code "39") (name "L12") (class "Default")
      (node (ref "B13") (pin "L1") (pinfunction "L1_L1") (pintype "bidirectional"))
      (node (ref "B13") (pin "L2") (pinfunction "L2_L2") (pintype "bidirectional"))
      (node (ref "R25") (pin "1") (pinfunction "1_1") (pintype "passive"))
    )
    (net (code "40") (name "L13") (class "Default")
      (node (ref "B14") (pin "L1") (pinfunction "L1_L1") (pintype "bidirectional"))
      (node (ref "B14") (pin "L2") (pinfunction "L2_L2") (pintype "bidirectional"))
      (node (ref "R24") (pin "1") (pinfunction "1_1") (pintype "passive"))
    )
    (net (code "41") (name "L14") (class "Default")
      (node (ref "B15") (pin "L1") (pinfunction "L1_L1") (pintype "bidirectional"))
      (node (ref "B15") (pin "L2") (pinfunction "L2_L2") (pintype "bidirectional"))
      (node (ref "R23") (pin "1") (pinfunction "1_1") (pintype "passive"))
    )
    (net (code "42") (name "L15") (class "Default")
      (node (ref "B16") (pin "L1") (pinfunction "L1_L1") (pintype "bidirectional"))
      (node (ref "B16") (pin "L2") (pinfunction "L2_L2") (pintype "bidirectional"))
      (node (ref "R22") (pin "1") (pinfunction "1_1") (pintype "passive"))
    )
    (net (code "43") (name "Net-(D1-A)") (class "Default")
      (node (ref "D1") (pin "2") (pinfunction "A_2") (pintype "passive"))
      (node (ref "OK4") (pin "4") (pinfunction "C_4") (pintype "passive"))
      (node (ref "X1") (pin "3") (pinfunction "F_3") (pintype "passive"))
    )
    (net (code "44") (name "Net-(D1-C)") (class "Default")
      (node (ref "D1") (pin "1") (pinfunction "C_1") (pintype "passive"))
      (node (ref "OK4") (pin "3") (pinfunction "A_3") (pintype "passive"))
      (node (ref "R20") (pin "2") (pinfunction "2_2") (pintype "passive"))
    )
    (net (code "45") (name "Net-(D2-A)") (class "Default")
      (node (ref "D2") (pin "2") (pinfunction "A_2") (pintype "passive"))
      (node (ref "OK4") (pin "2") (pinfunction "C_2") (pintype "passive"))
      (node (ref "X1") (pin "4") (pinfunction "F_4") (pintype "passive"))
    )
    (net (code "46") (name "Net-(D2-C)") (class "Default")
      (node (ref "D2") (pin "1") (pinfunction "C_1") (pintype "passive"))
      (node (ref "OK4") (pin "1") (pinfunction "A_1") (pintype "passive"))
      (node (ref "R19") (pin "2") (pinfunction "2_2") (pintype "passive"))
    )
    (net (code "47") (name "Net-(D3-A)") (class "Default")
      (node (ref "D3") (pin "2") (pinfunction "A_2") (pintype "passive"))
      (node (ref "OK3") (pin "4") (pinfunction "C_4") (pintype "passive"))
      (node (ref "X1") (pin "5") (pinfunction "F_5") (pintype "passive"))
    )
    (net (code "48") (name "Net-(D3-C)") (class "Default")
      (node (ref "D3") (pin "1") (pinfunction "C_1") (pintype "passive"))
      (node (ref "OK3") (pin "3") (pinfunction "A_3") (pintype "passive"))
      (node (ref "R18") (pin "2") (pinfunction "2_2") (pintype "passive"))
    )
    (net (code "49") (name "Net-(D4-A)") (class "Default")
      (node (ref "D4") (pin "2") (pinfunction "A_2") (pintype "passive"))
      (node (ref "OK3") (pin "2") (pinfunction "C_2") (pintype "passive"))
      (node (ref "X1") (pin "6") (pinfunction "F_6") (pintype "passive"))
    )
    (net (code "50") (name "Net-(D4-C)") (class "Default")
      (node (ref "D4") (pin "1") (pinfunction "C_1") (pintype "passive"))
      (node (ref "OK3") (pin "1") (pinfunction "A_1") (pintype "passive"))
      (node (ref "R17") (pin "2") (pinfunction "2_2") (pintype "passive"))
    )
    (net (code "51") (name "Net-(D5-A)") (class "Default")
      (node (ref "D5") (pin "2") (pinfunction "A_2") (pintype "passive"))
      (node (ref "OK2") (pin "4") (pinfunction "C_4") (pintype "passive"))
      (node (ref "X1") (pin "7") (pinfunction "F_7") (pintype "passive"))
    )
    (net (code "52") (name "Net-(D5-C)") (class "Default")
      (node (ref "D5") (pin "1") (pinfunction "C_1") (pintype "passive"))
      (node (ref "OK2") (pin "3") (pinfunction "A_3") (pintype "passive"))
      (node (ref "R16") (pin "2") (pinfunction "2_2") (pintype "passive"))
    )
    (net (code "53") (name "Net-(D6-A)") (class "Default")
      (node (ref "D6") (pin "2") (pinfunction "A_2") (pintype "passive"))
      (node (ref "OK2") (pin "2") (pinfunction "C_2") (pintype "passive"))
      (node (ref "X1") (pin "8") (pinfunction "F_8") (pintype "passive"))
    )
    (net (code "54") (name "Net-(D6-C)") (class "Default")
      (node (ref "D6") (pin "1") (pinfunction "C_1") (pintype "passive"))
      (node (ref "OK2") (pin "1") (pinfunction "A_1") (pintype "passive"))
      (node (ref "R15") (pin "2") (pinfunction "2_2") (pintype "passive"))
    )
    (net (code "55") (name "Net-(D7-A)") (class "Default")
      (node (ref "D7") (pin "2") (pinfunction "A_2") (pintype "passive"))
      (node (ref "OK1") (pin "4") (pinfunction "C_4") (pintype "passive"))
      (node (ref "X1") (pin "9") (pinfunction "F_9") (pintype "passive"))
    )
    (net (code "56") (name "Net-(D7-C)") (class "Default")
      (node (ref "D7") (pin "1") (pinfunction "C_1") (pintype "passive"))
      (node (ref "OK1") (pin "3") (pinfunction "A_3") (pintype "passive"))
      (node (ref "R13") (pin "2") (pinfunction "2_2") (pintype "passive"))
    )
    (net (code "57") (name "Net-(D8-A)") (class "Default")
      (node (ref "D8") (pin "2") (pinfunction "A_2") (pintype "passive"))
      (node (ref "OK1") (pin "2") (pinfunction "C_2") (pintype "passive"))
      (node (ref "X1") (pin "10") (pinfunction "F_10") (pintype "passive"))
    )
    (net (code "58") (name "Net-(D8-C)") (class "Default")
      (node (ref "D8") (pin "1") (pinfunction "C_1") (pintype "passive"))
      (node (ref "OK1") (pin "1") (pinfunction "A_1") (pintype "passive"))
      (node (ref "R14") (pin "2") (pinfunction "2_2") (pintype "passive"))
    )
    (net (code "59") (name "Net-(GND-Pad5V)") (class "Default")
      (node (ref "GND") (pin "5V") (pinfunction "5V_5V") (pintype "bidirectional"))
      (node (ref "L4") (pin "1") (pinfunction "1_1") (pintype "passive"))
      (node (ref "PC2") (pin "+") (pinfunction "+_+") (pintype "passive"))
    )
    (net (code "60") (name "Net-(IC1-I1)") (class "Default")
      (node (ref "IC1") (pin "1") (pinfunction "I1_1") (pintype "input"))
      (node (ref "IC2") (pin "1") (pinfunction "GPB0_1") (pintype "bidirectional"))
    )
    (net (code "61") (name "Net-(IC1-I2)") (class "Default")
      (node (ref "IC1") (pin "2") (pinfunction "I2_2") (pintype "input"))
      (node (ref "IC2") (pin "2") (pinfunction "GPB1_2") (pintype "bidirectional"))
    )
    (net (code "62") (name "Net-(IC1-I3)") (class "Default")
      (node (ref "IC1") (pin "3") (pinfunction "I3_3") (pintype "input"))
      (node (ref "IC2") (pin "3") (pinfunction "GPB2_3") (pintype "bidirectional"))
    )
    (net (code "63") (name "Net-(IC1-I4)") (class "Default")
      (node (ref "IC1") (pin "4") (pinfunction "I4_4") (pintype "input"))
      (node (ref "IC2") (pin "4") (pinfunction "GPB3_4") (pintype "bidirectional"))
    )
    (net (code "64") (name "Net-(IC1-I5)") (class "Default")
      (node (ref "IC1") (pin "5") (pinfunction "I5_5") (pintype "input"))
      (node (ref "IC2") (pin "5") (pinfunction "GPB4_5") (pintype "bidirectional"))
    )
    (net (code "65") (name "Net-(IC1-I6)") (class "Default")
      (node (ref "IC1") (pin "6") (pinfunction "I6_6") (pintype "input"))
      (node (ref "IC2") (pin "6") (pinfunction "GPB5_6") (pintype "bidirectional"))
    )
    (net (code "66") (name "Net-(IC1-I7)") (class "Default")
      (node (ref "IC1") (pin "7") (pinfunction "I7_7") (pintype "input"))
      (node (ref "IC2") (pin "7") (pinfunction "GPB6_7") (pintype "bidirectional"))
    )
    (net (code "67") (name "Net-(IC1-I8)") (class "Default")
      (node (ref "IC1") (pin "8") (pinfunction "I8_8") (pintype "input"))
      (node (ref "IC2") (pin "8") (pinfunction "GPB7_8") (pintype "bidirectional"))
    )
    (net (code "68") (name "Net-(IC1-O1)") (class "Default")
      (node (ref "IC1") (pin "18") (pinfunction "O1_18") (pintype "open_collector"))
      (node (ref "K1") (pin "16") (pinfunction "2_16") (pintype "passive"))
    )
    (net (code "69") (name "Net-(IC1-O2)") (class "Default")
      (node (ref "IC1") (pin "17") (pinfunction "O2_17") (pintype "open_collector"))
      (node (ref "K2") (pin "16") (pinfunction "2_16") (pintype "passive"))
    )
    (net (code "70") (name "Net-(IC1-O3)") (class "Default")
      (node (ref "IC1") (pin "16") (pinfunction "O3_16") (pintype "open_collector"))
      (node (ref "K3") (pin "16") (pinfunction "2_16") (pintype "passive"))
    )
    (net (code "71") (name "Net-(IC1-O4)") (class "Default")
      (node (ref "IC1") (pin "15") (pinfunction "O4_15") (pintype "open_collector"))
      (node (ref "K4") (pin "16") (pinfunction "2_16") (pintype "passive"))
    )
    (net (code "72") (name "Net-(IC1-O5)") (class "Default")
      (node (ref "IC1") (pin "14") (pinfunction "O5_14") (pintype "open_collector"))
      (node (ref "K5") (pin "16") (pinfunction "2_16") (pintype "passive"))
    )
    (net (code "73") (name "Net-(IC1-O6)") (class "Default")
      (node (ref "IC1") (pin "13") (pinfunction "O6_13") (pintype "open_collector"))
      (node (ref "K6") (pin "16") (pinfunction "2_16") (pintype "passive"))
    )
    (net (code "74") (name "Net-(IC1-O7)") (class "Default")
      (node (ref "IC1") (pin "12") (pinfunction "O7_12") (pintype "open_collector"))
      (node (ref "K7") (pin "16") (pinfunction "2_16") (pintype "passive"))
    )
    (net (code "75") (name "Net-(IC1-O8)") (class "Default")
      (node (ref "IC1") (pin "11") (pinfunction "O8_11") (pintype "open_collector"))
      (node (ref "K8") (pin "16") (pinfunction "2_16") (pintype "passive"))
    )
    (net (code "76") (name "Net-(IC2-GPA0)") (class "Default")
      (node (ref "IC2") (pin "21") (pinfunction "GPA0_21") (pintype "bidirectional"))
      (node (ref "OK1") (pin "8") (pinfunction "COL_8") (pintype "passive"))
    )
    (net (code "77") (name "Net-(IC2-GPA1)") (class "Default")
      (node (ref "IC2") (pin "22") (pinfunction "GPA1_22") (pintype "bidirectional"))
      (node (ref "OK1") (pin "6") (pinfunction "COL_6") (pintype "passive"))
    )
    (net (code "78") (name "Net-(IC2-GPA2)") (class "Default")
      (node (ref "IC2") (pin "23") (pinfunction "GPA2_23") (pintype "bidirectional"))
      (node (ref "OK2") (pin "8") (pinfunction "COL_8") (pintype "passive"))
    )
    (net (code "79") (name "Net-(IC2-GPA3)") (class "Default")
      (node (ref "IC2") (pin "24") (pinfunction "GPA3_24") (pintype "bidirectional"))
      (node (ref "OK2") (pin "6") (pinfunction "COL_6") (pintype "passive"))
    )
    (net (code "80") (name "Net-(IC2-GPA4)") (class "Default")
      (node (ref "IC2") (pin "25") (pinfunction "GPA4_25") (pintype "bidirectional"))
      (node (ref "OK3") (pin "8") (pinfunction "COL_8") (pintype "passive"))
    )
    (net (code "81") (name "Net-(IC2-GPA5)") (class "Default")
      (node (ref "IC2") (pin "26") (pinfunction "GPA5_26") (pintype "bidirectional"))
      (node (ref "OK3") (pin "6") (pinfunction "COL_6") (pintype "passive"))
    )
    (net (code "82") (name "Net-(IC2-GPA6)") (class "Default")
      (node (ref "IC2") (pin "27") (pinfunction "GPA6_27") (pintype "bidirectional"))
      (node (ref "OK4") (pin "8") (pinfunction "COL_8") (pintype "passive"))
    )
    (net (code "83") (name "Net-(IC2-GPA7)") (class "Default")
      (node (ref "IC2") (pin "28") (pinfunction "GPA7_28") (pintype "bidirectional"))
      (node (ref "OK4") (pin "6") (pinfunction "COL_6") (pintype "passive"))
    )
    (net (code "84") (name "Net-(IC3-L0)") (class "Default")
      (node (ref "IC3") (pin "6") (pinfunction "L0_6") (pintype "output"))
      (node (ref "R37") (pin "2") (pinfunction "2_2") (pintype "passive"))
    )
    (net (code "85") (name "Net-(IC3-L1)") (class "Default")
      (node (ref "IC3") (pin "7") (pinfunction "L1_7") (pintype "output"))
      (node (ref "R36") (pin "2") (pinfunction "2_2") (pintype "passive"))
    )
    (net (code "86") (name "Net-(IC3-L2)") (class "Default")
      (node (ref "IC3") (pin "8") (pinfunction "L2_8") (pintype "output"))
      (node (ref "R35") (pin "2") (pinfunction "2_2") (pintype "passive"))
    )
    (net (code "87") (name "Net-(IC3-L3)") (class "Default")
      (node (ref "IC3") (pin "9") (pinfunction "L3_9") (pintype "output"))
      (node (ref "R34") (pin "2") (pinfunction "2_2") (pintype "passive"))
    )
    (net (code "88") (name "Net-(IC3-L4)") (class "Default")
      (node (ref "IC3") (pin "10") (pinfunction "L4_10") (pintype "output"))
      (node (ref "R33") (pin "2") (pinfunction "2_2") (pintype "passive"))
    )
    (net (code "89") (name "Net-(IC3-L5)") (class "Default")
      (node (ref "IC3") (pin "11") (pinfunction "L5_11") (pintype "output"))
      (node (ref "R32") (pin "2") (pinfunction "2_2") (pintype "passive"))
    )
    (net (code "90") (name "Net-(IC3-L6)") (class "Default")
      (node (ref "IC3") (pin "12") (pinfunction "L6_12") (pintype "output"))
      (node (ref "R31") (pin "2") (pinfunction "2_2") (pintype "passive"))
    )
    (net (code "91") (name "Net-(IC3-L7)") (class "Default")
      (node (ref "IC3") (pin "13") (pinfunction "L7_13") (pintype "output"))
      (node (ref "R30") (pin "2") (pinfunction "2_2") (pintype "passive"))
    )
    (net (code "92") (name "Net-(IC3-L8)") (class "Default")
      (node (ref "IC3") (pin "15") (pinfunction "L8_15") (pintype "output"))
      (node (ref "R29") (pin "2") (pinfunction "2_2") (pintype "passive"))
    )
    (net (code "93") (name "Net-(IC3-L9)") (class "Default")
      (node (ref "IC3") (pin "16") (pinfunction "L9_16") (pintype "output"))
      (node (ref "R28") (pin "2") (pinfunction "2_2") (pintype "passive"))
    )
    (net (code "94") (name "Net-(IC3-L10)") (class "Default")
      (node (ref "IC3") (pin "17") (pinfunction "L10_17") (pintype "output"))
      (node (ref "R27") (pin "2") (pinfunction "2_2") (pintype "passive"))
    )
    (net (code "95") (name "Net-(IC3-L11)") (class "Default")
      (node (ref "IC3") (pin "18") (pinfunction "L11_18") (pintype "output"))
      (node (ref "R26") (pin "2") (pinfunction "2_2") (pintype "passive"))
    )
    (net (code "96") (name "Net-(IC3-L12)") (class "Default")
      (node (ref "IC3") (pin "19") (pinfunction "L12_19") (pintype "output"))
      (node (ref "R25") (pin "2") (pinfunction "2_2") (pintype "passive"))
    )
    (net (code "97") (name "Net-(IC3-L13)") (class "Default")
      (node (ref "IC3") (pin "20") (pinfunction "L13_20") (pintype "output"))
      (node (ref "R24") (pin "2") (pinfunction "2_2") (pintype "passive"))
    )
    (net (code "98") (name "Net-(IC3-L14)") (class "Default")
      (node (ref "IC3") (pin "21") (pinfunction "L14_21") (pintype "output"))
      (node (ref "R23") (pin "2") (pinfunction "2_2") (pintype "passive"))
    )
    (net (code "99") (name "Net-(IC3-L15)") (class "Default")
      (node (ref "IC3") (pin "22") (pinfunction "L15_22") (pintype "output"))
      (node (ref "R22") (pin "2") (pinfunction "2_2") (pintype "passive"))
    )
    (net (code "100") (name "Net-(JP3-Pad4)") (class "Default")
      (node (ref "JP3") (pin "4") (pinfunction "4_4") (pintype "passive"))
      (node (ref "JP5") (pin "4") (pinfunction "4_4") (pintype "passive"))
    )
    (net (code "101") (name "Net-(JP3-Pad5)") (class "Default")
      (node (ref "JP3") (pin "5") (pinfunction "5_5") (pintype "passive"))
      (node (ref "JP5") (pin "5") (pinfunction "5_5") (pintype "passive"))
    )
    (net (code "102") (name "Net-(JP3-Pad6)") (class "Default")
      (node (ref "JP3") (pin "6") (pinfunction "6_6") (pintype "passive"))
      (node (ref "JP5") (pin "6") (pinfunction "6_6") (pintype "passive"))
    )
    (net (code "103") (name "Net-(K1B-S)") (class "Default")
      (node (ref "K1") (pin "S1") (pinfunction "S_S1") (pintype "passive"))
      (node (ref "X1") (pin "23") (pinfunction "F_23") (pintype "passive"))
    )
    (net (code "104") (name "Net-(K2B-S)") (class "Default")
      (node (ref "K2") (pin "S1") (pinfunction "S_S1") (pintype "passive"))
      (node (ref "X1") (pin "22") (pinfunction "F_22") (pintype "passive"))
    )
    (net (code "105") (name "Net-(K3B-S)") (class "Default")
      (node (ref "K3") (pin "S1") (pinfunction "S_S1") (pintype "passive"))
      (node (ref "X1") (pin "21") (pinfunction "F_21") (pintype "passive"))
    )
    (net (code "106") (name "Net-(K4B-S)") (class "Default")
      (node (ref "K4") (pin "S1") (pinfunction "S_S1") (pintype "passive"))
      (node (ref "X1") (pin "20") (pinfunction "F_20") (pintype "passive"))
    )
    (net (code "107") (name "Net-(K5B-S)") (class "Default")
      (node (ref "K5") (pin "S1") (pinfunction "S_S1") (pintype "passive"))
      (node (ref "X1") (pin "19") (pinfunction "F_19") (pintype "passive"))
    )
    (net (code "108") (name "Net-(K6B-S)") (class "Default")
      (node (ref "K6") (pin "S1") (pinfunction "S_S1") (pintype "passive"))
      (node (ref "X1") (pin "18") (pinfunction "F_18") (pintype "passive"))
    )
    (net (code "109") (name "Net-(K7B-S)") (class "Default")
      (node (ref "K7") (pin "S1") (pinfunction "S_S1") (pintype "passive"))
      (node (ref "X1") (pin "17") (pinfunction "F_17") (pintype "passive"))
    )
    (net (code "110") (name "Net-(K8B-S)") (class "Default")
      (node (ref "K8") (pin "S1") (pinfunction "S_S1") (pintype "passive"))
      (node (ref "X1") (pin "16") (pinfunction "F_16") (pintype "passive"))
    )
    (net (code "111") (name "Net-(U$7-P$2)") (class "Default")
      (node (ref "R4") (pin "1") (pinfunction "1_1") (pintype "passive"))
      (node (ref "U$7") (pin "A2") (pinfunction "P$2_A2") (pintype "bidirectional"))
    )
    (net (code "112") (name "Net-(U$7-P$3)") (class "Default")
      (node (ref "R3") (pin "1") (pinfunction "1_1") (pintype "passive"))
      (node (ref "U$7") (pin "A3") (pinfunction "P$3_A3") (pintype "bidirectional"))
    )
    (net (code "113") (name "RES") (class "Default")
      (node (ref "GND") (pin "RES") (pinfunction "RES_RES") (pintype "bidirectional"))
      (node (ref "RESET") (pin "1") (pinfunction "1_1") (pintype "passive"))
      (node (ref "RESETA") (pin "1") (pinfunction "1_1") (pintype "passive"))
    )
    (net (code "114") (name "SDI_MOSI") (class "Default")
      (node (ref "JP6") (pin "2") (pinfunction "2_2") (pintype "passive"))
      (node (ref "SERIAL1") (pin "8") (pinfunction "8_8") (pintype "passive"))
    )
    (net (code "115") (name "SDI_SCLK") (class "Default")
      (node (ref "JP6") (pin "1") (pinfunction "1_1") (pintype "passive"))
      (node (ref "SERIAL1") (pin "7") (pinfunction "7_7") (pintype "passive"))
    )
    (net (code "116") (name "SLIDER_IN") (class "Default")
      (node (ref "C7") (pin "1") (pinfunction "1_1") (pintype "passive"))
      (node (ref "GND") (pin "A0") (pinfunction "A0_A0") (pintype "bidirectional"))
      (node (ref "POT1") (pin "2A") (pinfunction "S_2A") (pintype "passive"))
      (node (ref "SERIAL1") (pin "5") (pinfunction "5_5") (pintype "passive"))
    )
    (net (code "117") (name "VIN") (class "Default")
      (node (ref "GND") (pin "VIN") (pinfunction "VIN_VIN") (pintype "bidirectional"))
    )
    (net (code "118") (name "unconnected-(B1-PadL3)") (class "Default")
      (node (ref "B1") (pin "L3") (pinfunction "L3_L3") (pintype "bidirectional"))
    )
    (net (code "119") (name "unconnected-(B1-PadL4)") (class "Default")
      (node (ref "B1") (pin "L4") (pinfunction "L4_L4") (pintype "bidirectional"))
    )
    (net (code "120") (name "unconnected-(B1-PadLC2)") (class "Default")
      (node (ref "B1") (pin "LC2") (pinfunction "LC2_LC2") (pintype "bidirectional"))
    )
    (net (code "121") (name "unconnected-(B2-PadL3)") (class "Default")
      (node (ref "B2") (pin "L3") (pinfunction "L3_L3") (pintype "bidirectional"))
    )
    (net (code "122") (name "unconnected-(B2-PadL4)") (class "Default")
      (node (ref "B2") (pin "L4") (pinfunction "L4_L4") (pintype "bidirectional"))
    )
    (net (code "123") (name "unconnected-(B2-PadLC2)") (class "Default")
      (node (ref "B2") (pin "LC2") (pinfunction "LC2_LC2") (pintype "bidirectional"))
    )
    (net (code "124") (name "unconnected-(B3-PadL3)") (class "Default")
      (node (ref "B3") (pin "L3") (pinfunction "L3_L3") (pintype "bidirectional"))
    )
    (net (code "125") (name "unconnected-(B3-PadL4)") (class "Default")
      (node (ref "B3") (pin "L4") (pinfunction "L4_L4") (pintype "bidirectional"))
    )
    (net (code "126") (name "unconnected-(B3-PadLC2)") (class "Default")
      (node (ref "B3") (pin "LC2") (pinfunction "LC2_LC2") (pintype "bidirectional"))
    )
    (net (code "127") (name "unconnected-(B4-PadL3)") (class "Default")
      (node (ref "B4") (pin "L3") (pinfunction "L3_L3") (pintype "bidirectional"))
    )
    (net (code "128") (name "unconnected-(B4-PadL4)") (class "Default")
      (node (ref "B4") (pin "L4") (pinfunction "L4_L4") (pintype "bidirectional"))
    )
    (net (code "129") (name "unconnected-(B4-PadLC2)") (class "Default")
      (node (ref "B4") (pin "LC2") (pinfunction "LC2_LC2") (pintype "bidirectional"))
    )
    (net (code "130") (name "unconnected-(B5-PadL3)") (class "Default")
      (node (ref "B5") (pin "L3") (pinfunction "L3_L3") (pintype "bidirectional"))
    )
    (net (code "131") (name "unconnected-(B5-PadL4)") (class "Default")
      (node (ref "B5") (pin "L4") (pinfunction "L4_L4") (pintype "bidirectional"))
    )
    (net (code "132") (name "unconnected-(B5-PadLC2)") (class "Default")
      (node (ref "B5") (pin "LC2") (pinfunction "LC2_LC2") (pintype "bidirectional"))
    )
    (net (code "133") (name "unconnected-(B6-PadL3)") (class "Default")
      (node (ref "B6") (pin "L3") (pinfunction "L3_L3") (pintype "bidirectional"))
    )
    (net (code "134") (name "unconnected-(B6-PadL4)") (class "Default")
      (node (ref "B6") (pin "L4") (pinfunction "L4_L4") (pintype "bidirectional"))
    )
    (net (code "135") (name "unconnected-(B6-PadLC2)") (class "Default")
      (node (ref "B6") (pin "LC2") (pinfunction "LC2_LC2") (pintype "bidirectional"))
    )
    (net (code "136") (name "unconnected-(B7-PadL3)") (class "Default")
      (node (ref "B7") (pin "L3") (pinfunction "L3_L3") (pintype "bidirectional"))
    )
    (net (code "137") (name "unconnected-(B7-PadL4)") (class "Default")
      (node (ref "B7") (pin "L4") (pinfunction "L4_L4") (pintype "bidirectional"))
    )
    (net (code "138") (name "unconnected-(B7-PadLC2)") (class "Default")
      (node (ref "B7") (pin "LC2") (pinfunction "LC2_LC2") (pintype "bidirectional"))
    )
    (net (code "139") (name "unconnected-(B8-PadL3)") (class "Default")
      (node (ref "B8") (pin "L3") (pinfunction "L3_L3") (pintype "bidirectional"))
    )
    (net (code "140") (name "unconnected-(B8-PadL4)") (class "Default")
      (node (ref "B8") (pin "L4") (pinfunction "L4_L4") (pintype "bidirectional"))
    )
    (net (code "141") (name "unconnected-(B8-PadLC2)") (class "Default")
      (node (ref "B8") (pin "LC2") (pinfunction "LC2_LC2") (pintype "bidirectional"))
    )
    (net (code "142") (name "unconnected-(B9-PadL3)") (class "Default")
      (node (ref "B9") (pin "L3") (pinfunction "L3_L3") (pintype "bidirectional"))
    )
    (net (code "143") (name "unconnected-(B9-PadL4)") (class "Default")
      (node (ref "B9") (pin "L4") (pinfunction "L4_L4") (pintype "bidirectional"))
    )
    (net (code "144") (name "unconnected-(B9-PadLC2)") (class "Default")
      (node (ref "B9") (pin "LC2") (pinfunction "LC2_LC2") (pintype "bidirectional"))
    )
    (net (code "145") (name "unconnected-(B10-PadL3)") (class "Default")
      (node (ref "B10") (pin "L3") (pinfunction "L3_L3") (pintype "bidirectional"))
    )
    (net (code "146") (name "unconnected-(B10-PadL4)") (class "Default")
      (node (ref "B10") (pin "L4") (pinfunction "L4_L4") (pintype "bidirectional"))
    )
    (net (code "147") (name "unconnected-(B10-PadLC2)") (class "Default")
      (node (ref "B10") (pin "LC2") (pinfunction "LC2_LC2") (pintype "bidirectional"))
    )
    (net (code "148") (name "unconnected-(B11-PadL3)") (class "Default")
      (node (ref "B11") (pin "L3") (pinfunction "L3_L3") (pintype "bidirectional"))
    )
    (net (code "149") (name "unconnected-(B11-PadL4)") (class "Default")
      (node (ref "B11") (pin "L4") (pinfunction "L4_L4") (pintype "bidirectional"))
    )
    (net (code "150") (name "unconnected-(B11-PadLC2)") (class "Default")
      (node (ref "B11") (pin "LC2") (pinfunction "LC2_LC2") (pintype "bidirectional"))
    )
    (net (code "151") (name "unconnected-(B12-PadL3)") (class "Default")
      (node (ref "B12") (pin "L3") (pinfunction "L3_L3") (pintype "bidirectional"))
    )
    (net (code "152") (name "unconnected-(B12-PadL4)") (class "Default")
      (node (ref "B12") (pin "L4") (pinfunction "L4_L4") (pintype "bidirectional"))
    )
    (net (code "153") (name "unconnected-(B12-PadLC2)") (class "Default")
      (node (ref "B12") (pin "LC2") (pinfunction "LC2_LC2") (pintype "bidirectional"))
    )
    (net (code "154") (name "unconnected-(B13-PadL3)") (class "Default")
      (node (ref "B13") (pin "L3") (pinfunction "L3_L3") (pintype "bidirectional"))
    )
    (net (code "155") (name "unconnected-(B13-PadL4)") (class "Default")
      (node (ref "B13") (pin "L4") (pinfunction "L4_L4") (pintype "bidirectional"))
    )
    (net (code "156") (name "unconnected-(B13-PadLC2)") (class "Default")
      (node (ref "B13") (pin "LC2") (pinfunction "LC2_LC2") (pintype "bidirectional"))
    )
    (net (code "157") (name "unconnected-(B14-PadL3)") (class "Default")
      (node (ref "B14") (pin "L3") (pinfunction "L3_L3") (pintype "bidirectional"))
    )
    (net (code "158") (name "unconnected-(B14-PadL4)") (class "Default")
      (node (ref "B14") (pin "L4") (pinfunction "L4_L4") (pintype "bidirectional"))
    )
    (net (code "159") (name "unconnected-(B14-PadLC2)") (class "Default")
      (node (ref "B14") (pin "LC2") (pinfunction "LC2_LC2") (pintype "bidirectional"))
    )
    (net (code "160") (name "unconnected-(B15-PadL3)") (class "Default")
      (node (ref "B15") (pin "L3") (pinfunction "L3_L3") (pintype "bidirectional"))
    )
    (net (code "161") (name "unconnected-(B15-PadL4)") (class "Default")
      (node (ref "B15") (pin "L4") (pinfunction "L4_L4") (pintype "bidirectional"))
    )
    (net (code "162") (name "unconnected-(B15-PadLC2)") (class "Default")
      (node (ref "B15") (pin "LC2") (pinfunction "LC2_LC2") (pintype "bidirectional"))
    )
    (net (code "163") (name "unconnected-(B16-PadL3)") (class "Default")
      (node (ref "B16") (pin "L3") (pinfunction "L3_L3") (pintype "bidirectional"))
    )
    (net (code "164") (name "unconnected-(B16-PadL4)") (class "Default")
      (node (ref "B16") (pin "L4") (pinfunction "L4_L4") (pintype "bidirectional"))
    )
    (net (code "165") (name "unconnected-(B16-PadLC2)") (class "Default")
      (node (ref "B16") (pin "LC2") (pinfunction "LC2_LC2") (pintype "bidirectional"))
    )
    (net (code "166") (name "unconnected-(GND-*D5-PadD5)") (class "Default")
      (node (ref "GND") (pin "D5") (pinfunction "*D5_D5") (pintype "bidirectional"))
    )
    (net (code "167") (name "unconnected-(GND-*D6-PadD6)") (class "Default")
      (node (ref "GND") (pin "D6") (pinfunction "*D6_D6") (pintype "bidirectional"))
    )
    (net (code "168") (name "unconnected-(GND-*D9-PadD9)") (class "Default")
      (node (ref "GND") (pin "D9") (pinfunction "*D9_D9") (pintype "bidirectional"))
    )
    (net (code "169") (name "unconnected-(GND-*D10-PadD10)") (class "Default")
      (node (ref "GND") (pin "D10") (pinfunction "*D10_D10") (pintype "bidirectional"))
    )
    (net (code "170") (name "unconnected-(GND-*D11-PadD11)") (class "Default")
      (node (ref "GND") (pin "D11") (pinfunction "*D11_D11") (pintype "bidirectional"))
    )
    (net (code "171") (name "unconnected-(GND-Pad3.3V)") (class "Default")
      (node (ref "GND") (pin "3.3V") (pinfunction "3.3V_3.3V") (pintype "bidirectional"))
    )
    (net (code "172") (name "unconnected-(GND-PadA2)") (class "Default")
      (node (ref "GND") (pin "A2") (pinfunction "A2_A2") (pintype "bidirectional"))
    )
    (net (code "173") (name "unconnected-(GND-PadA3)") (class "Default")
      (node (ref "GND") (pin "A3") (pinfunction "A3_A3") (pintype "bidirectional"))
    )
    (net (code "174") (name "unconnected-(GND-PadA4)") (class "Default")
      (node (ref "GND") (pin "A4") (pinfunction "A4_A4") (pintype "bidirectional"))
    )
    (net (code "175") (name "unconnected-(GND-PadA5)") (class "Default")
      (node (ref "GND") (pin "A5") (pinfunction "A5_A5") (pintype "bidirectional"))
    )
    (net (code "176") (name "unconnected-(GND-PadAREF)") (class "Default")
      (node (ref "GND") (pin "AREF") (pinfunction "AREF_AREF") (pintype "bidirectional"))
    )
    (net (code "177") (name "unconnected-(GND-PadD4)") (class "Default")
      (node (ref "GND") (pin "D4") (pinfunction "D4_D4") (pintype "bidirectional"))
    )
    (net (code "178") (name "unconnected-(GND-PadD8)") (class "Default")
      (node (ref "GND") (pin "D8") (pinfunction "D8_D8") (pintype "bidirectional"))
    )
    (net (code "179") (name "unconnected-(GND-PadD12)") (class "Default")
      (node (ref "GND") (pin "D12") (pinfunction "D12_D12") (pintype "bidirectional"))
    )
    (net (code "180") (name "unconnected-(GND-PadD13)") (class "Default")
      (node (ref "GND") (pin "D13") (pinfunction "D13_D13") (pintype "bidirectional"))
    )
    (net (code "181") (name "unconnected-(GND-PadRX)") (class "Default")
      (node (ref "GND") (pin "RX") (pinfunction "RX_RX") (pintype "bidirectional"))
    )
    (net (code "182") (name "unconnected-(GND-PadTX)") (class "Default")
      (node (ref "GND") (pin "TX") (pinfunction "TX_TX") (pintype "bidirectional"))
    )
    (net (code "183") (name "unconnected-(IC2-INTA-Pad20)") (class "Default")
      (node (ref "IC2") (pin "20") (pinfunction "INTA_20") (pintype "output"))
    )
    (net (code "184") (name "unconnected-(IC2-INTB-Pad19)") (class "Default")
      (node (ref "IC2") (pin "19") (pinfunction "INTB_19") (pintype "output"))
    )
    (net (code "185") (name "unconnected-(IC4-INTA-Pad20)") (class "Default")
      (node (ref "IC4") (pin "20") (pinfunction "INTA_20") (pintype "output"))
    )
    (net (code "186") (name "unconnected-(IC4-INTB-Pad19)") (class "Default")
      (node (ref "IC4") (pin "19") (pinfunction "INTB_19") (pintype "output"))
    )
    (net (code "187") (name "unconnected-(JP1-Pad1)") (class "Default")
      (node (ref "JP1") (pin "1") (pinfunction "1_1") (pintype "passive"))
    )
    (net (code "188") (name "unconnected-(JP1-Pad2)") (class "Default")
      (node (ref "JP1") (pin "2") (pinfunction "2_2") (pintype "passive"))
    )
    (net (code "189") (name "unconnected-(JP3-Pad2)") (class "Default")
      (node (ref "JP3") (pin "2") (pinfunction "2_2") (pintype "passive"))
    )
    (net (code "190") (name "unconnected-(JP5-Pad2)") (class "Default")
      (node (ref "JP5") (pin "2") (pinfunction "2_2") (pintype "passive"))
    )
    (net (code "191") (name "unconnected-(K1B-O-PadO1)") (class "Default")
      (node (ref "K1") (pin "O1") (pinfunction "O_O1") (pintype "passive"))
    )
    (net (code "192") (name "unconnected-(K1C-O-PadO2)") (class "Default")
      (node (ref "K1") (pin "O2") (pinfunction "O_O2") (pintype "passive"))
    )
    (net (code "193") (name "unconnected-(K1C-S-PadS2)") (class "Default")
      (node (ref "K1") (pin "S2") (pinfunction "S_S2") (pintype "passive"))
    )
    (net (code "194") (name "unconnected-(K2B-O-PadO1)") (class "Default")
      (node (ref "K2") (pin "O1") (pinfunction "O_O1") (pintype "passive"))
    )
    (net (code "195") (name "unconnected-(K2C-O-PadO2)") (class "Default")
      (node (ref "K2") (pin "O2") (pinfunction "O_O2") (pintype "passive"))
    )
    (net (code "196") (name "unconnected-(K2C-S-PadS2)") (class "Default")
      (node (ref "K2") (pin "S2") (pinfunction "S_S2") (pintype "passive"))
    )
    (net (code "197") (name "unconnected-(K3B-O-PadO1)") (class "Default")
      (node (ref "K3") (pin "O1") (pinfunction "O_O1") (pintype "passive"))
    )
    (net (code "198") (name "unconnected-(K3C-O-PadO2)") (class "Default")
      (node (ref "K3") (pin "O2") (pinfunction "O_O2") (pintype "passive"))
    )
    (net (code "199") (name "unconnected-(K3C-S-PadS2)") (class "Default")
      (node (ref "K3") (pin "S2") (pinfunction "S_S2") (pintype "passive"))
    )
    (net (code "200") (name "unconnected-(K4B-O-PadO1)") (class "Default")
      (node (ref "K4") (pin "O1") (pinfunction "O_O1") (pintype "passive"))
    )
    (net (code "201") (name "unconnected-(K4C-O-PadO2)") (class "Default")
      (node (ref "K4") (pin "O2") (pinfunction "O_O2") (pintype "passive"))
    )
    (net (code "202") (name "unconnected-(K4C-S-PadS2)") (class "Default")
      (node (ref "K4") (pin "S2") (pinfunction "S_S2") (pintype "passive"))
    )
    (net (code "203") (name "unconnected-(K5B-O-PadO1)") (class "Default")
      (node (ref "K5") (pin "O1") (pinfunction "O_O1") (pintype "passive"))
    )
    (net (code "204") (name "unconnected-(K5C-O-PadO2)") (class "Default")
      (node (ref "K5") (pin "O2") (pinfunction "O_O2") (pintype "passive"))
    )
    (net (code "205") (name "unconnected-(K5C-S-PadS2)") (class "Default")
      (node (ref "K5") (pin "S2") (pinfunction "S_S2") (pintype "passive"))
    )
    (net (code "206") (name "unconnected-(K6B-O-PadO1)") (class "Default")
      (node (ref "K6") (pin "O1") (pinfunction "O_O1") (pintype "passive"))
    )
    (net (code "207") (name "unconnected-(K6C-O-PadO2)") (class "Default")
      (node (ref "K6") (pin "O2") (pinfunction "O_O2") (pintype "passive"))
    )
    (net (code "208") (name "unconnected-(K6C-S-PadS2)") (class "Default")
      (node (ref "K6") (pin "S2") (pinfunction "S_S2") (pintype "passive"))
    )
    (net (code "209") (name "unconnected-(K7B-O-PadO1)") (class "Default")
      (node (ref "K7") (pin "O1") (pinfunction "O_O1") (pintype "passive"))
    )
    (net (code "210") (name "unconnected-(K7C-O-PadO2)") (class "Default")
      (node (ref "K7") (pin "O2") (pinfunction "O_O2") (pintype "passive"))
    )
    (net (code "211") (name "unconnected-(K7C-S-PadS2)") (class "Default")
      (node (ref "K7") (pin "S2") (pinfunction "S_S2") (pintype "passive"))
    )
    (net (code "212") (name "unconnected-(K8B-O-PadO1)") (class "Default")
      (node (ref "K8") (pin "O1") (pinfunction "O_O1") (pintype "passive"))
    )
    (net (code "213") (name "unconnected-(K8C-O-PadO2)") (class "Default")
      (node (ref "K8") (pin "O2") (pinfunction "O_O2") (pintype "passive"))
    )
    (net (code "214") (name "unconnected-(K8C-S-PadS2)") (class "Default")
      (node (ref "K8") (pin "S2") (pinfunction "S_S2") (pintype "passive"))
    )
  )
)
